# Page_1.net
KiCad netlist of a schematic drawn in Altium Designer
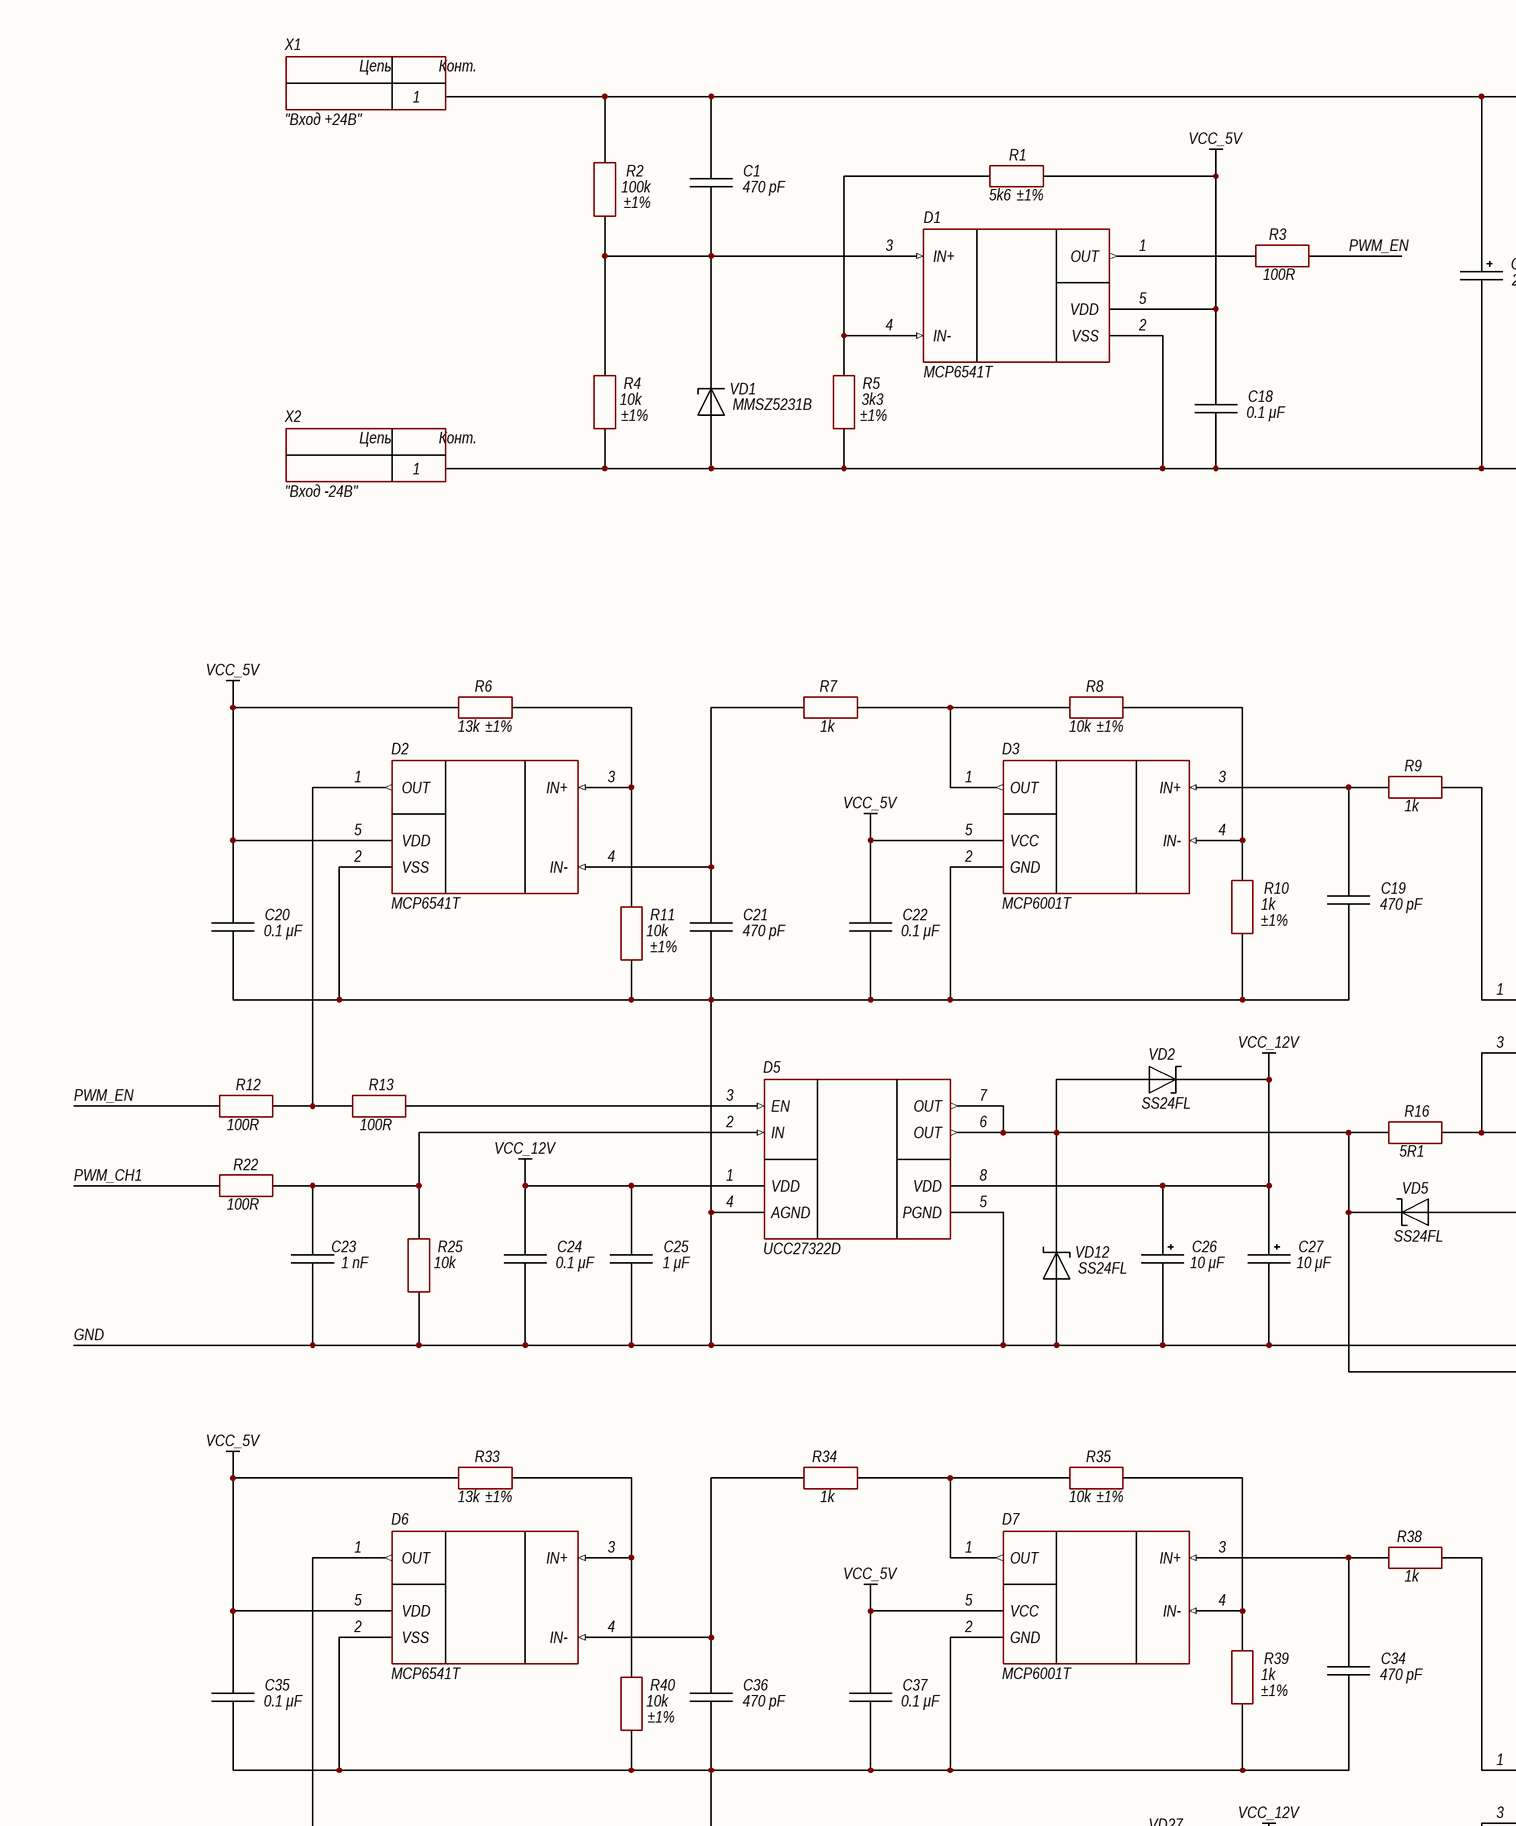
[diagram p0: Page 1.SchDoc, top left]
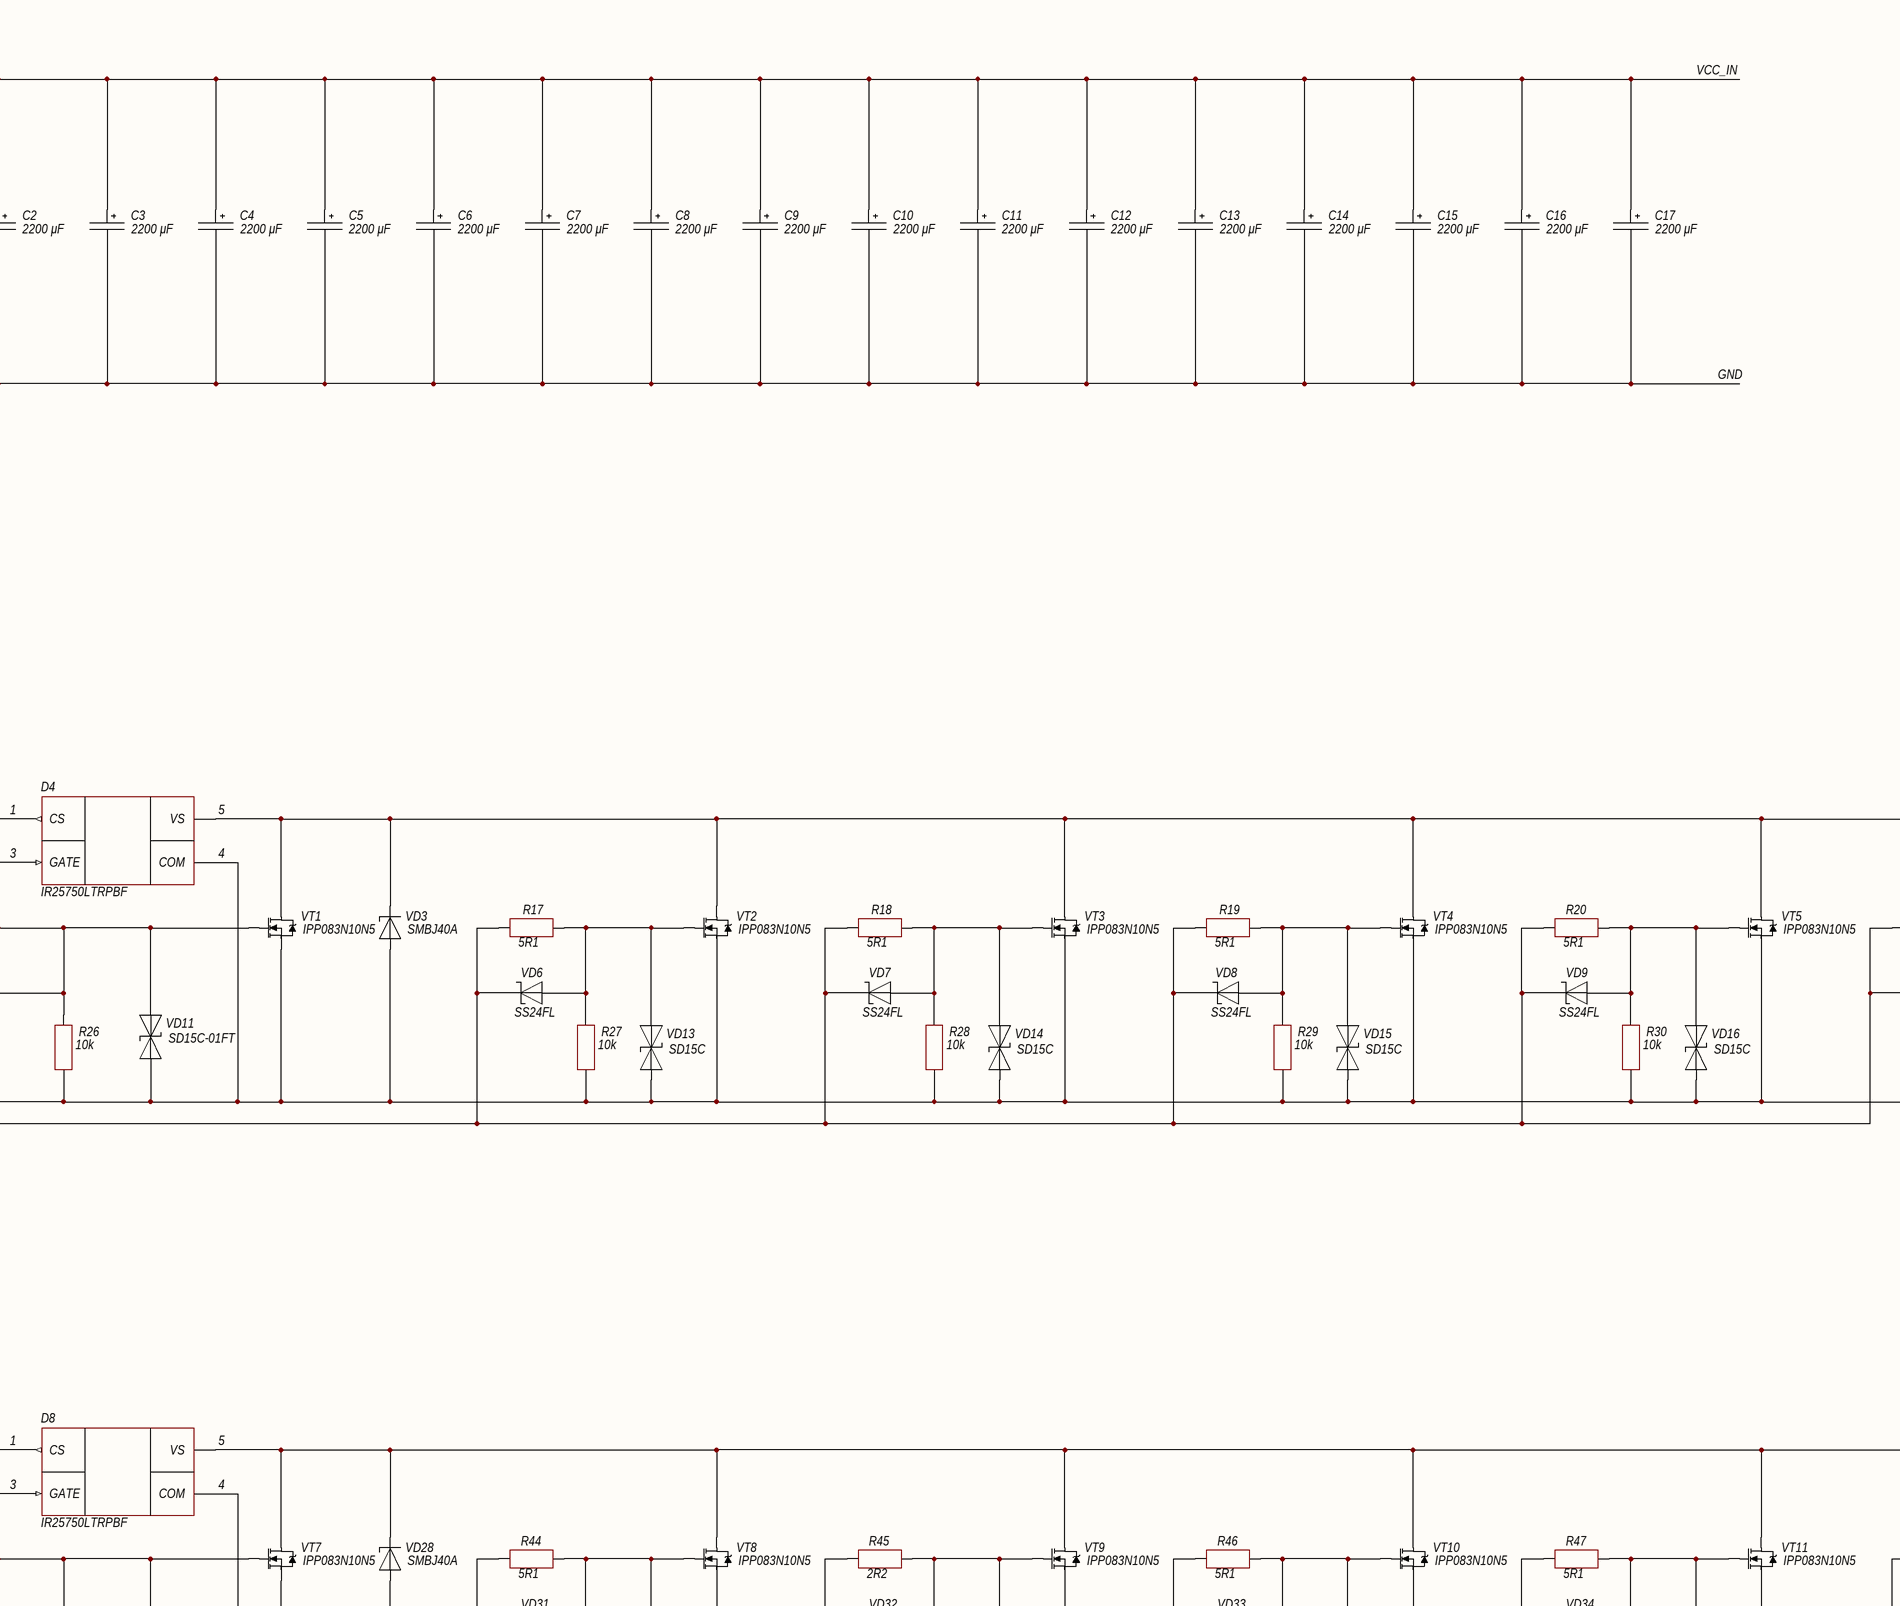
[diagram p1: Page 1.SchDoc, top middle]
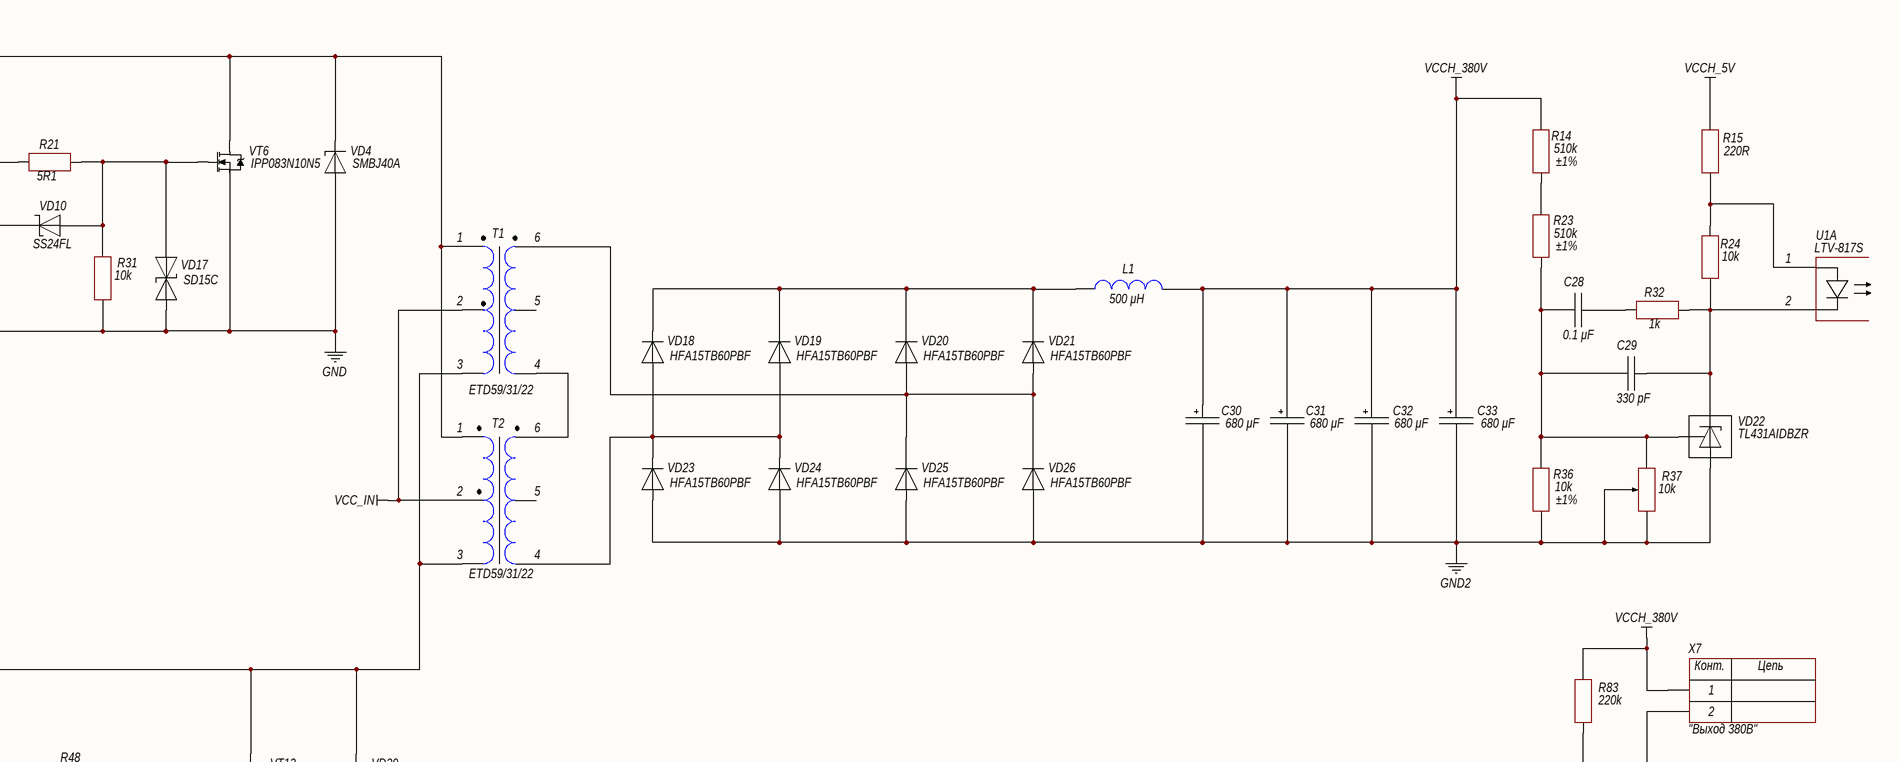
[diagram p2: Page 1.SchDoc, top right]
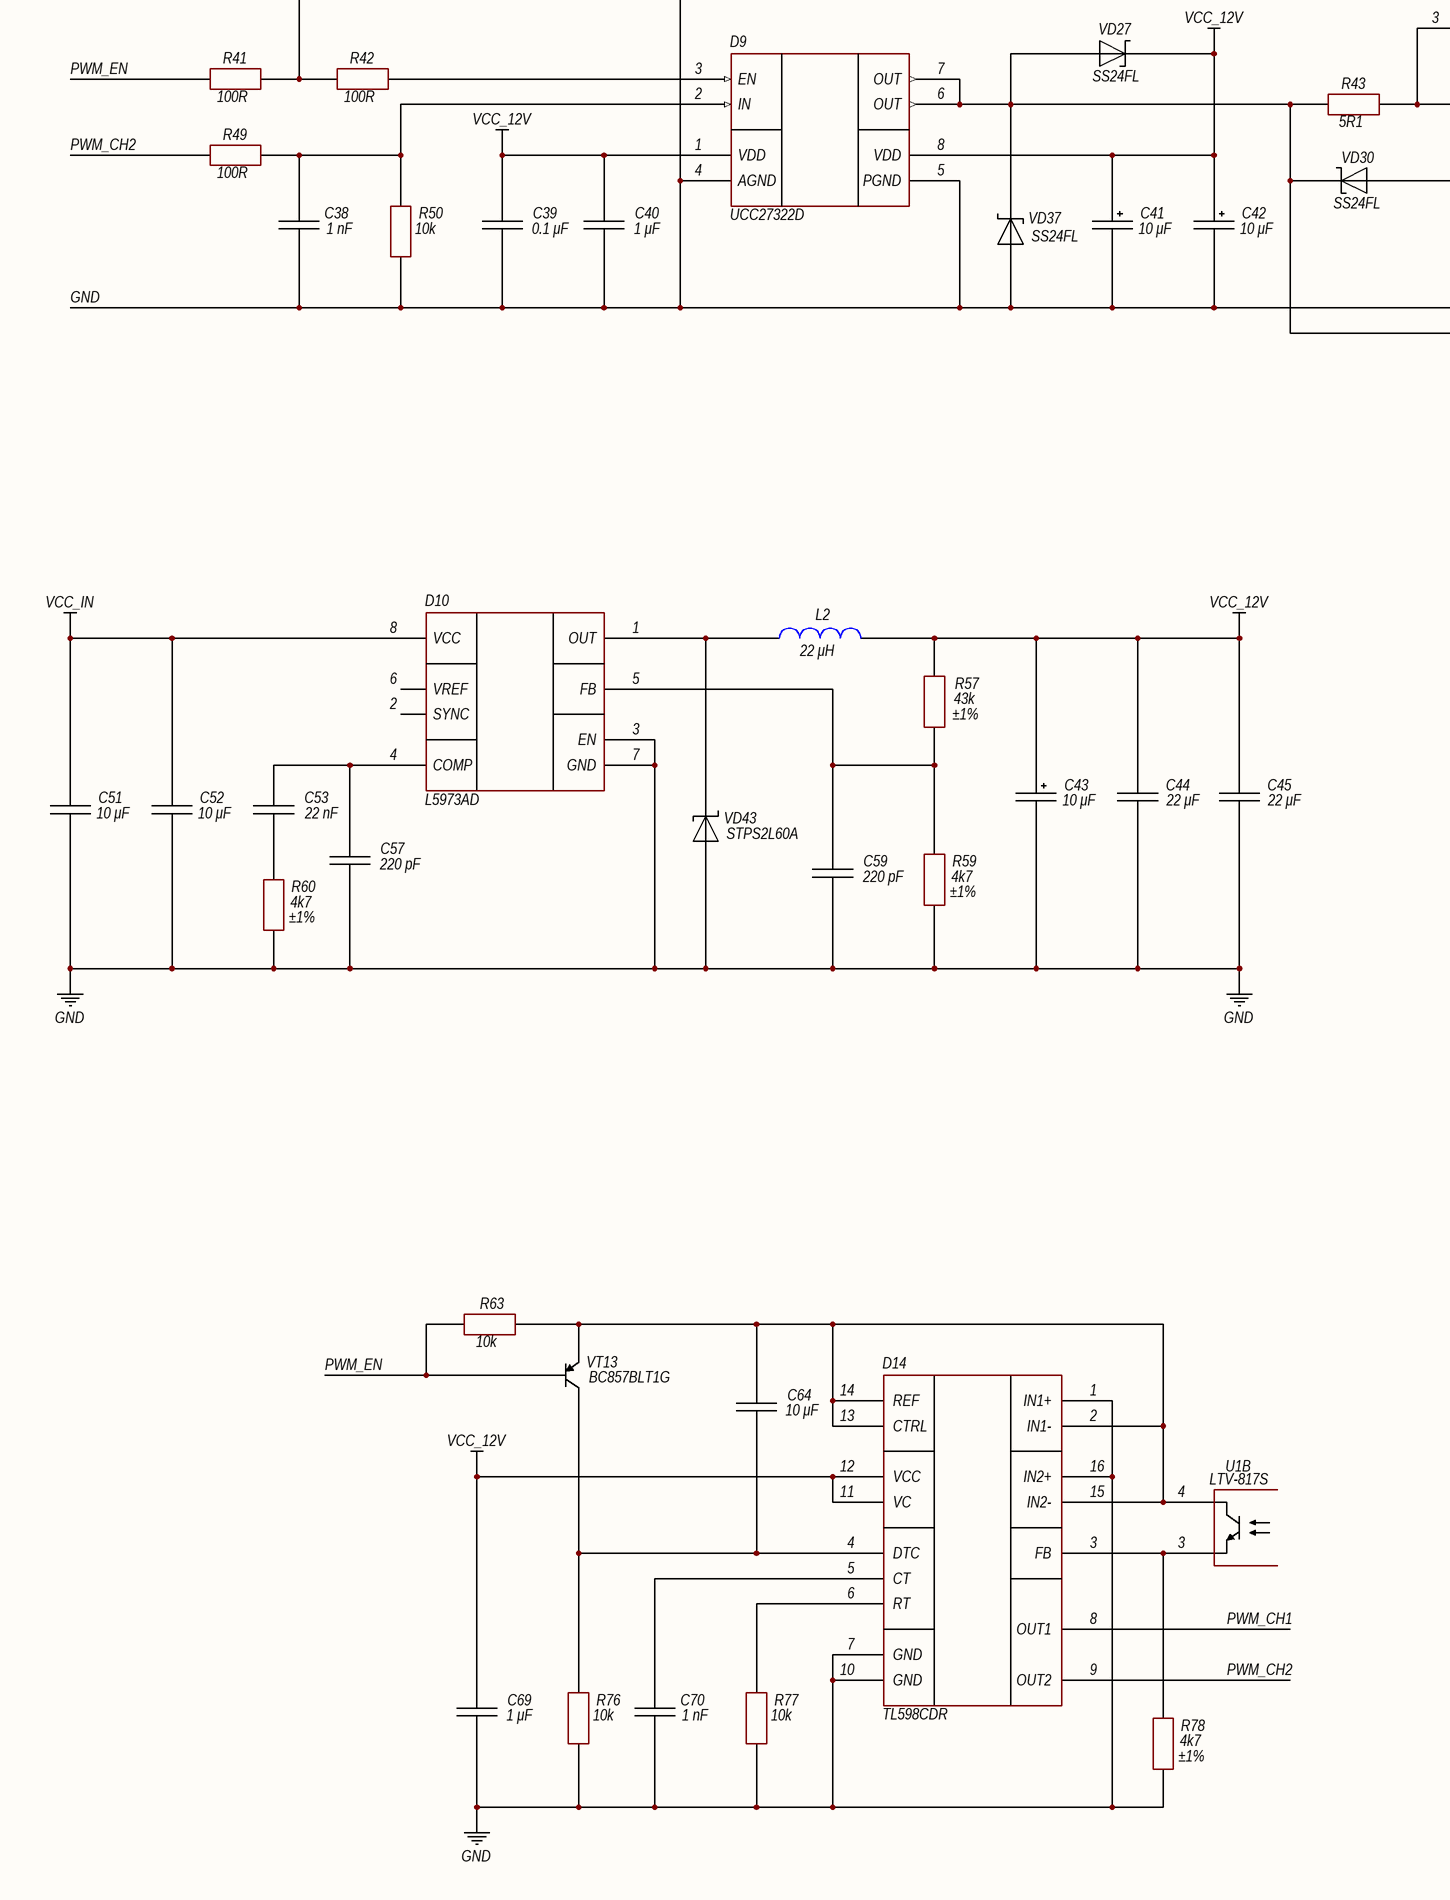
[diagram p3: Page 1.SchDoc, bottom left]
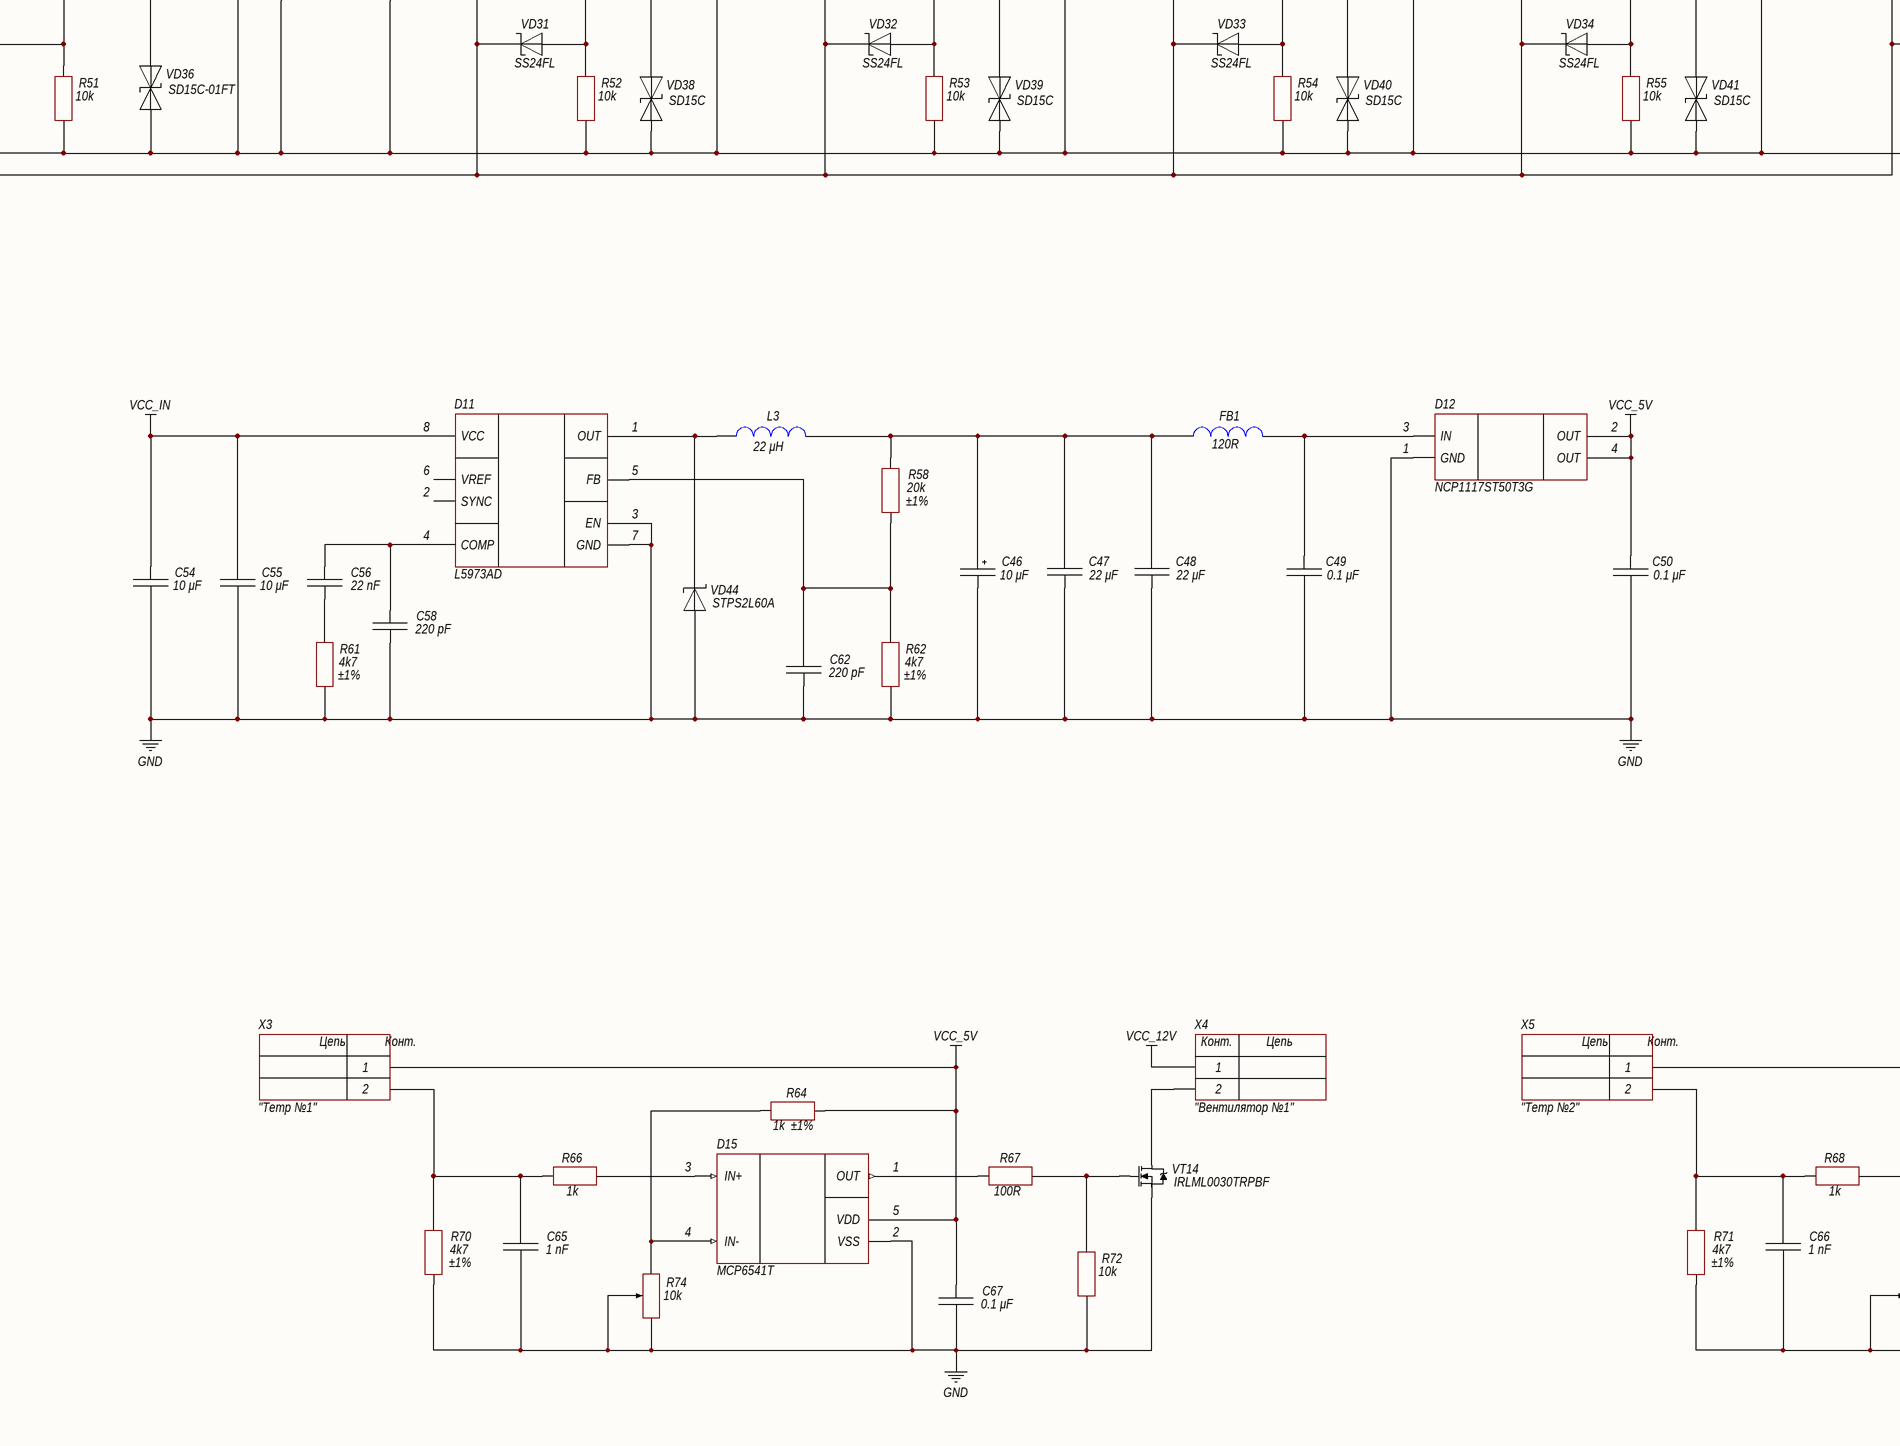
[diagram p4: Page 1.SchDoc, bottom middle]
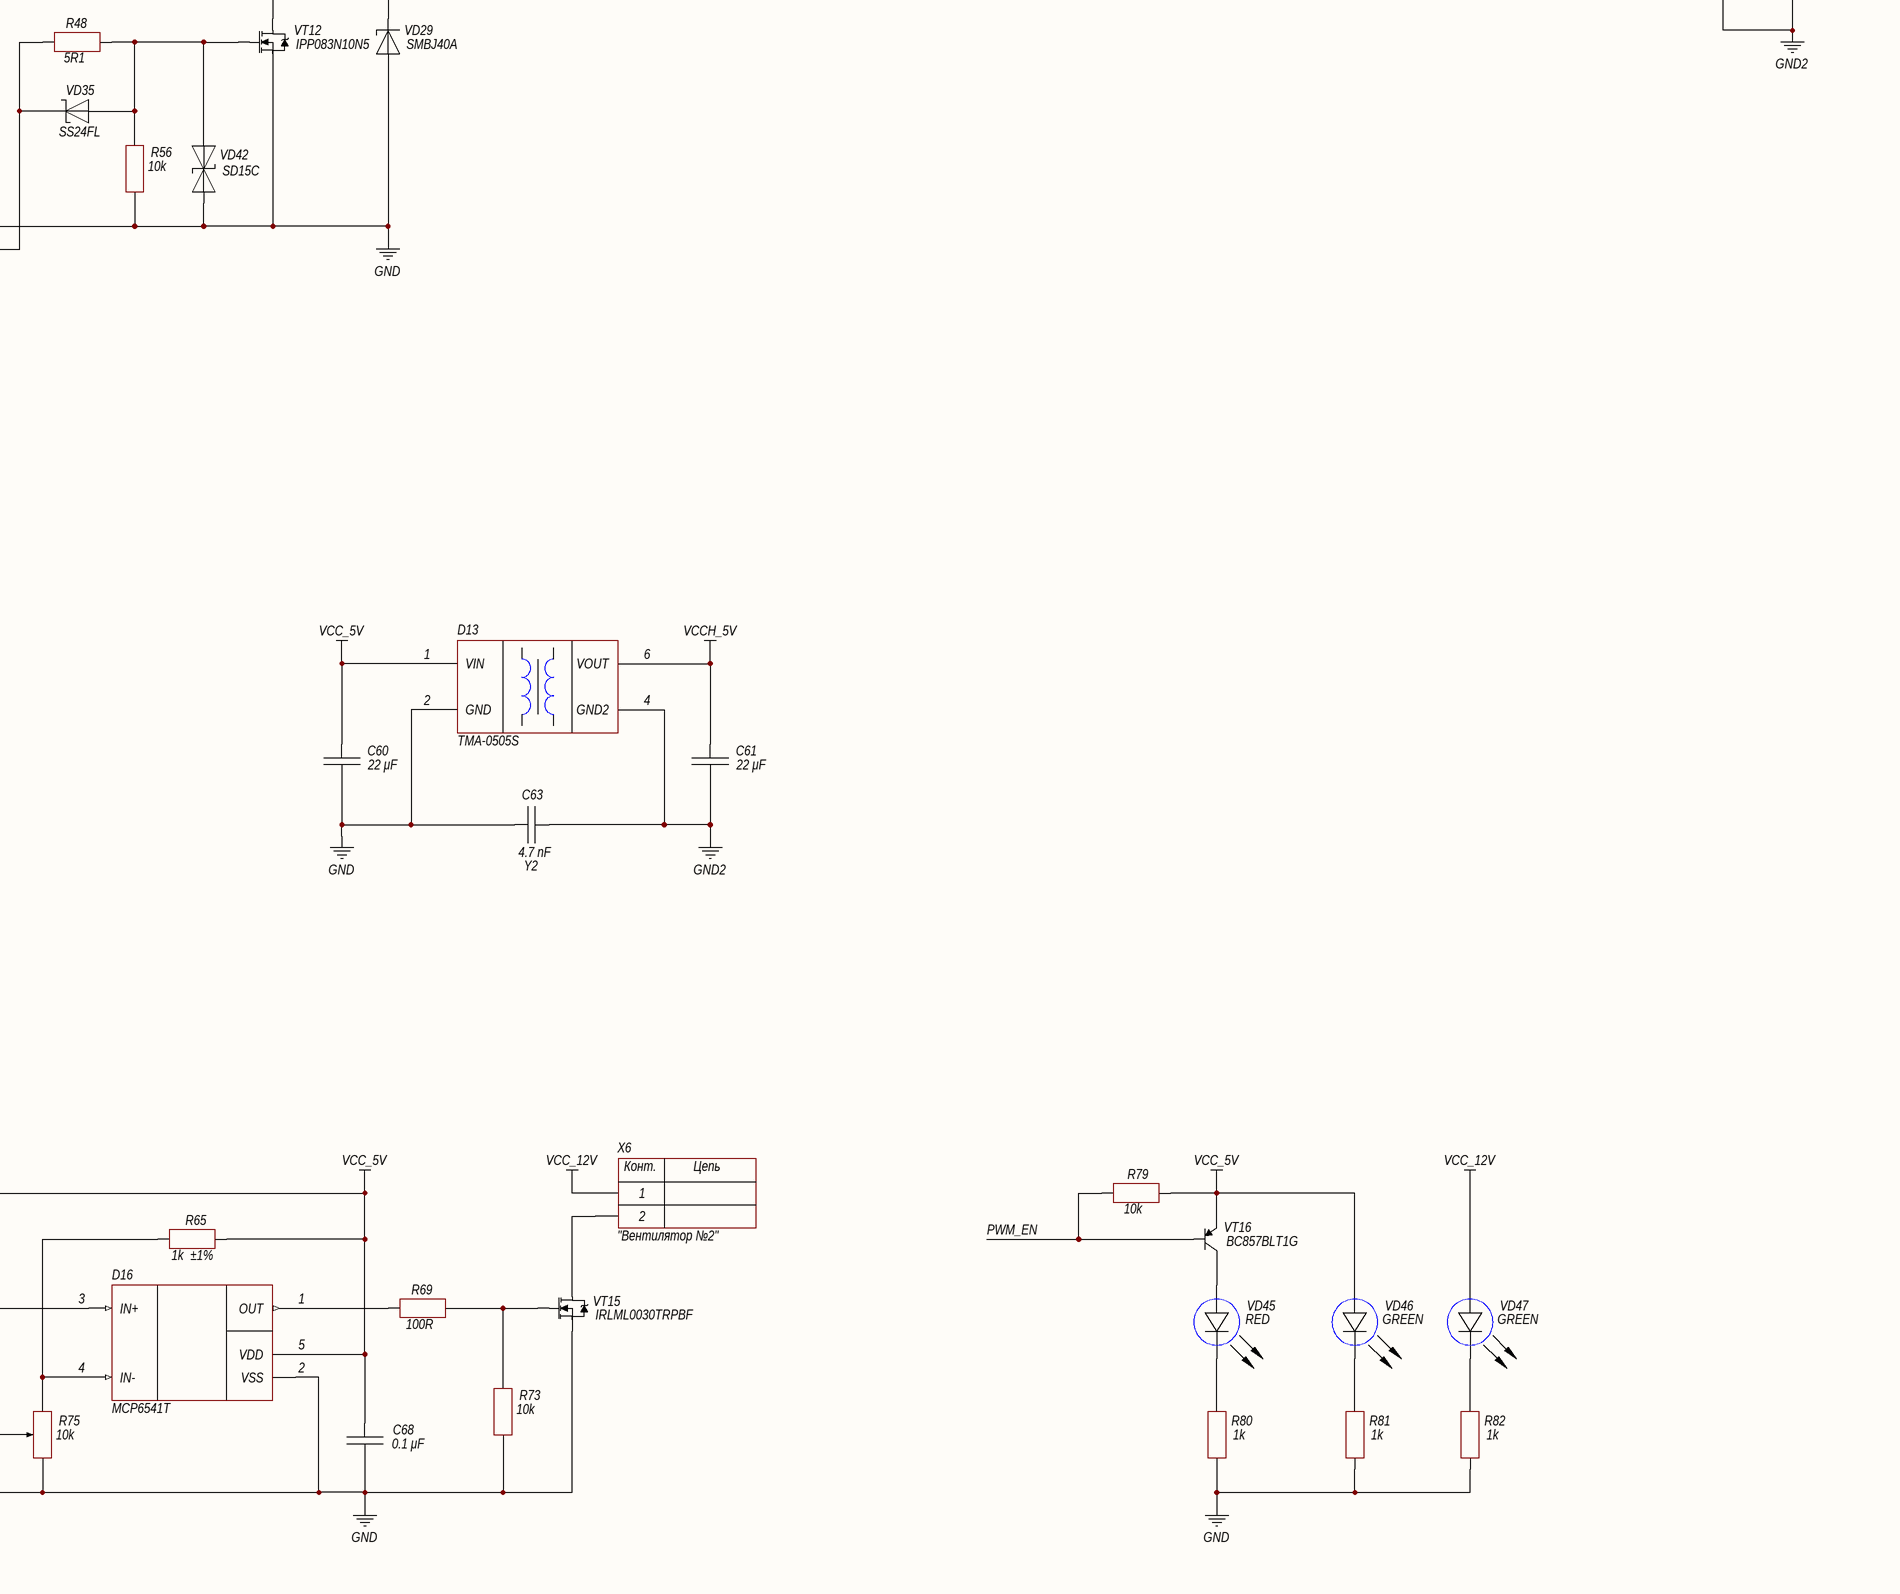
[diagram p5: Page 1.SchDoc, bottom right]

(export (version "E")
  (design (tool "Eeschema 10.0.6"))
  (components
    (comp (ref "C1")
      (value "470 pF")
      (footprint "CH0805C")
      (fields (field (name "MANUFACTURER") "Yageo"))
      (libsource (lib "Discrete") (part "Capacitor"))
    )
    (comp (ref "C2")
      (value "2200 μF")
      (footprint "D16C7.5H25")
      (fields (field (name "MANUFACTURER") "Epcos"))
      (libsource (lib "Discrete") (part "AlumCap"))
    )
    (comp (ref "C3")
      (value "2200 μF")
      (footprint "D16C7.5H25")
      (fields (field (name "MANUFACTURER") "Epcos"))
      (libsource (lib "Discrete") (part "AlumCap"))
    )
    (comp (ref "C4")
      (value "2200 μF")
      (footprint "D16C7.5H25")
      (fields (field (name "MANUFACTURER") "Epcos"))
      (libsource (lib "Discrete") (part "AlumCap"))
    )
    (comp (ref "C5")
      (value "2200 μF")
      (footprint "D16C7.5H25")
      (fields (field (name "MANUFACTURER") "Epcos"))
      (libsource (lib "Discrete") (part "AlumCap"))
    )
    (comp (ref "C6")
      (value "2200 μF")
      (footprint "D16C7.5H25")
      (fields (field (name "MANUFACTURER") "Epcos"))
      (libsource (lib "Discrete") (part "AlumCap"))
    )
    (comp (ref "C7")
      (value "2200 μF")
      (footprint "D16C7.5H25")
      (fields (field (name "MANUFACTURER") "Epcos"))
      (libsource (lib "Discrete") (part "AlumCap"))
    )
    (comp (ref "C8")
      (value "2200 μF")
      (footprint "D16C7.5H25")
      (fields (field (name "MANUFACTURER") "Epcos"))
      (libsource (lib "Discrete") (part "AlumCap"))
    )
    (comp (ref "C9")
      (value "2200 μF")
      (footprint "D16C7.5H25")
      (fields (field (name "MANUFACTURER") "Epcos"))
      (libsource (lib "Discrete") (part "AlumCap"))
    )
    (comp (ref "C10")
      (value "2200 μF")
      (footprint "D16C7.5H25")
      (fields (field (name "MANUFACTURER") "Epcos"))
      (libsource (lib "Discrete") (part "AlumCap"))
    )
    (comp (ref "C11")
      (value "2200 μF")
      (footprint "D16C7.5H25")
      (fields (field (name "MANUFACTURER") "Epcos"))
      (libsource (lib "Discrete") (part "AlumCap"))
    )
    (comp (ref "C12")
      (value "2200 μF")
      (footprint "D16C7.5H25")
      (fields (field (name "MANUFACTURER") "Epcos"))
      (libsource (lib "Discrete") (part "AlumCap"))
    )
    (comp (ref "C13")
      (value "2200 μF")
      (footprint "D16C7.5H25")
      (fields (field (name "MANUFACTURER") "Epcos"))
      (libsource (lib "Discrete") (part "AlumCap"))
    )
    (comp (ref "C14")
      (value "2200 μF")
      (footprint "D16C7.5H25")
      (fields (field (name "MANUFACTURER") "Epcos"))
      (libsource (lib "Discrete") (part "AlumCap"))
    )
    (comp (ref "C15")
      (value "2200 μF")
      (footprint "D16C7.5H25")
      (fields (field (name "MANUFACTURER") "Epcos"))
      (libsource (lib "Discrete") (part "AlumCap"))
    )
    (comp (ref "C16")
      (value "2200 μF")
      (footprint "D16C7.5H25")
      (fields (field (name "MANUFACTURER") "Epcos"))
      (libsource (lib "Discrete") (part "AlumCap"))
    )
    (comp (ref "C17")
      (value "2200 μF")
      (footprint "D16C7.5H25")
      (fields (field (name "MANUFACTURER") "Epcos"))
      (libsource (lib "Discrete") (part "AlumCap"))
    )
    (comp (ref "C18")
      (value "0.1 μF")
      (footprint "CH0805C")
      (fields (field (name "MANUFACTURER") "Yageo"))
      (libsource (lib "Discrete") (part "Capacitor"))
    )
    (comp (ref "C19")
      (value "470 pF")
      (footprint "CH0805C")
      (fields (field (name "MANUFACTURER") "Yageo"))
      (libsource (lib "Discrete") (part "Capacitor"))
    )
    (comp (ref "C20")
      (value "0.1 μF")
      (footprint "CH0805C")
      (fields (field (name "MANUFACTURER") "Yageo"))
      (libsource (lib "Discrete") (part "Capacitor"))
    )
    (comp (ref "C21")
      (value "470 pF")
      (footprint "CH0805C")
      (fields (field (name "MANUFACTURER") "Yageo"))
      (libsource (lib "Discrete") (part "Capacitor"))
    )
    (comp (ref "C22")
      (value "0.1 μF")
      (footprint "CH0805C")
      (fields (field (name "MANUFACTURER") "Yageo"))
      (libsource (lib "Discrete") (part "Capacitor"))
    )
    (comp (ref "C23")
      (value "1 nF")
      (footprint "CH0805C")
      (fields (field (name "MANUFACTURER") "Yageo"))
      (libsource (lib "Discrete") (part "Capacitor"))
    )
    (comp (ref "C24")
      (value "0.1 μF")
      (footprint "CH0805C")
      (fields (field (name "MANUFACTURER") "Yageo"))
      (libsource (lib "Discrete") (part "Capacitor"))
    )
    (comp (ref "C25")
      (value "1 μF")
      (footprint "CH0805C")
      (fields (field (name "MANUFACTURER") "Yageo"))
      (libsource (lib "Discrete") (part "Capacitor"))
    )
    (comp (ref "C26")
      (value "10 μF")
      (footprint "TANTAL_C")
      (fields (field (name "MANUFACTURER") "Vishay Sprague"))
      (libsource (lib "Discrete") (part "TantalCap"))
    )
    (comp (ref "C27")
      (value "10 μF")
      (footprint "TANTAL_C")
      (fields (field (name "MANUFACTURER") "Vishay Sprague"))
      (libsource (lib "Discrete") (part "TantalCap"))
    )
    (comp (ref "C28")
      (value "0.1 μF")
      (footprint "CH0805C")
      (fields (field (name "MANUFACTURER") "Yageo"))
      (libsource (lib "Discrete") (part "Capacitor"))
    )
    (comp (ref "C29")
      (value "330 pF")
      (footprint "CH0805C")
      (fields (field (name "MANUFACTURER") "Yageo"))
      (libsource (lib "Discrete") (part "Capacitor"))
    )
    (comp (ref "C30")
      (value "680 μF")
      (footprint "D35C10.5H50")
      (fields (field (name "MANUFACTURER") "EPCOS"))
      (libsource (lib "Discrete") (part "AlumCap"))
    )
    (comp (ref "C31")
      (value "680 μF")
      (footprint "D35C10.5H50")
      (fields (field (name "MANUFACTURER") "EPCOS"))
      (libsource (lib "Discrete") (part "AlumCap"))
    )
    (comp (ref "C32")
      (value "680 μF")
      (footprint "D35C10.5H50")
      (fields (field (name "MANUFACTURER") "EPCOS"))
      (libsource (lib "Discrete") (part "AlumCap"))
    )
    (comp (ref "C33")
      (value "680 μF")
      (footprint "D35C10.5H50")
      (fields (field (name "MANUFACTURER") "EPCOS"))
      (libsource (lib "Discrete") (part "AlumCap"))
    )
    (comp (ref "C34")
      (value "470 pF")
      (footprint "CH0805C")
      (fields (field (name "MANUFACTURER") "Yageo"))
      (libsource (lib "Discrete") (part "Capacitor"))
    )
    (comp (ref "C35")
      (value "0.1 μF")
      (footprint "CH0805C")
      (fields (field (name "MANUFACTURER") "Yageo"))
      (libsource (lib "Discrete") (part "Capacitor"))
    )
    (comp (ref "C36")
      (value "470 pF")
      (footprint "CH0805C")
      (fields (field (name "MANUFACTURER") "Yageo"))
      (libsource (lib "Discrete") (part "Capacitor"))
    )
    (comp (ref "C37")
      (value "0.1 μF")
      (footprint "CH0805C")
      (fields (field (name "MANUFACTURER") "Yageo"))
      (libsource (lib "Discrete") (part "Capacitor"))
    )
    (comp (ref "C38")
      (value "1 nF")
      (footprint "CH0805C")
      (fields (field (name "MANUFACTURER") "Yageo"))
      (libsource (lib "Discrete") (part "Capacitor"))
    )
    (comp (ref "C39")
      (value "0.1 μF")
      (footprint "CH0805C")
      (fields (field (name "MANUFACTURER") "Yageo"))
      (libsource (lib "Discrete") (part "Capacitor"))
    )
    (comp (ref "C40")
      (value "1 μF")
      (footprint "CH0805C")
      (fields (field (name "MANUFACTURER") "Yageo"))
      (libsource (lib "Discrete") (part "Capacitor"))
    )
    (comp (ref "C41")
      (value "10 μF")
      (footprint "TANTAL_C")
      (fields (field (name "MANUFACTURER") "Vishay Sprague"))
      (libsource (lib "Discrete") (part "TantalCap"))
    )
    (comp (ref "C42")
      (value "10 μF")
      (footprint "TANTAL_C")
      (fields (field (name "MANUFACTURER") "Vishay Sprague"))
      (libsource (lib "Discrete") (part "TantalCap"))
    )
    (comp (ref "C43")
      (value "10 μF")
      (footprint "TANTAL_C")
      (fields (field (name "MANUFACTURER") "Vishay Sprague"))
      (libsource (lib "Discrete") (part "TantalCap"))
    )
    (comp (ref "C44")
      (value "22 μF")
      (footprint "CH1206C")
      (fields (field (name "MANUFACTURER") "Yageo"))
      (libsource (lib "Discrete") (part "Capacitor"))
    )
    (comp (ref "C45")
      (value "22 μF")
      (footprint "CH1206C")
      (fields (field (name "MANUFACTURER") "Yageo"))
      (libsource (lib "Discrete") (part "Capacitor"))
    )
    (comp (ref "C46")
      (value "10 μF")
      (footprint "TANTAL_C")
      (fields (field (name "MANUFACTURER") "Vishay Sprague"))
      (libsource (lib "Discrete") (part "TantalCap"))
    )
    (comp (ref "C47")
      (value "22 μF")
      (footprint "CH1206C")
      (fields (field (name "MANUFACTURER") "Yageo"))
      (libsource (lib "Discrete") (part "Capacitor"))
    )
    (comp (ref "C48")
      (value "22 μF")
      (footprint "CH1206C")
      (fields (field (name "MANUFACTURER") "Yageo"))
      (libsource (lib "Discrete") (part "Capacitor"))
    )
    (comp (ref "C49")
      (value "0.1 μF")
      (footprint "CH0805C")
      (fields (field (name "MANUFACTURER") "Yageo"))
      (libsource (lib "Discrete") (part "Capacitor"))
    )
    (comp (ref "C50")
      (value "0.1 μF")
      (footprint "CH0805C")
      (fields (field (name "MANUFACTURER") "Yageo"))
      (libsource (lib "Discrete") (part "Capacitor"))
    )
    (comp (ref "C51")
      (value "10 μF")
      (footprint "CH1206C")
      (fields (field (name "MANUFACTURER") "Yageo"))
      (libsource (lib "Discrete") (part "Capacitor"))
    )
    (comp (ref "C52")
      (value "10 μF")
      (footprint "CH1206C")
      (fields (field (name "MANUFACTURER") "Yageo"))
      (libsource (lib "Discrete") (part "Capacitor"))
    )
    (comp (ref "C53")
      (value "22 nF")
      (footprint "CH0805C")
      (fields (field (name "MANUFACTURER") "Yageo"))
      (libsource (lib "Discrete") (part "Capacitor"))
    )
    (comp (ref "C54")
      (value "10 μF")
      (footprint "CH1206C")
      (fields (field (name "MANUFACTURER") "Yageo"))
      (libsource (lib "Discrete") (part "Capacitor"))
    )
    (comp (ref "C55")
      (value "10 μF")
      (footprint "CH1206C")
      (fields (field (name "MANUFACTURER") "Yageo"))
      (libsource (lib "Discrete") (part "Capacitor"))
    )
    (comp (ref "C56")
      (value "22 nF")
      (footprint "CH0805C")
      (fields (field (name "MANUFACTURER") "Yageo"))
      (libsource (lib "Discrete") (part "Capacitor"))
    )
    (comp (ref "C57")
      (value "220 pF")
      (footprint "CH0805C")
      (fields (field (name "MANUFACTURER") "Yageo"))
      (libsource (lib "Discrete") (part "Capacitor"))
    )
    (comp (ref "C58")
      (value "220 pF")
      (footprint "CH0805C")
      (fields (field (name "MANUFACTURER") "Yageo"))
      (libsource (lib "Discrete") (part "Capacitor"))
    )
    (comp (ref "C59")
      (value "220 pF")
      (footprint "CH0805C")
      (fields (field (name "MANUFACTURER") "Yageo"))
      (libsource (lib "Discrete") (part "Capacitor"))
    )
    (comp (ref "C60")
      (value "22 μF")
      (footprint "CH1206C")
      (fields (field (name "MANUFACTURER") "Yageo"))
      (libsource (lib "Discrete") (part "Capacitor"))
    )
    (comp (ref "C61")
      (value "22 μF")
      (footprint "CH1206C")
      (fields (field (name "MANUFACTURER") "Yageo"))
      (libsource (lib "Discrete") (part "Capacitor"))
    )
    (comp (ref "C62")
      (value "220 pF")
      (footprint "CH0805C")
      (fields (field (name "MANUFACTURER") "Yageo"))
      (libsource (lib "Discrete") (part "Capacitor"))
    )
    (comp (ref "C63")
      (value "4.7 nF")
      (footprint "CAP: B32021")
      (fields (field (name "MANUFACTURER") "EPCOS (TDK)") (field (name "COMPONENTKIND") "Y2"))
      (libsource (lib "Discrete") (part "Capacitor"))
    )
    (comp (ref "C64")
      (value "10 μF")
      (footprint "CH0805C")
      (fields (field (name "MANUFACTURER") "Yageo"))
      (libsource (lib "Discrete") (part "Capacitor"))
    )
    (comp (ref "C65")
      (value "1 nF")
      (footprint "CH0805C")
      (fields (field (name "MANUFACTURER") "Yageo"))
      (libsource (lib "Discrete") (part "Capacitor"))
    )
    (comp (ref "C66")
      (value "1 nF")
      (footprint "CH0805C")
      (fields (field (name "MANUFACTURER") "Yageo"))
      (libsource (lib "Discrete") (part "Capacitor"))
    )
    (comp (ref "C67")
      (value "0.1 μF")
      (footprint "CH0805C")
      (fields (field (name "MANUFACTURER") "Yageo"))
      (libsource (lib "Discrete") (part "Capacitor"))
    )
    (comp (ref "C68")
      (value "0.1 μF")
      (footprint "CH0805C")
      (fields (field (name "MANUFACTURER") "Yageo"))
      (libsource (lib "Discrete") (part "Capacitor"))
    )
    (comp (ref "C69")
      (value "1 μF")
      (footprint "CH0805C")
      (fields (field (name "MANUFACTURER") "Yageo"))
      (libsource (lib "Discrete") (part "Capacitor"))
    )
    (comp (ref "C70")
      (value "1 nF")
      (footprint "CH0805C")
      (fields (field (name "MANUFACTURER") "Yageo"))
      (libsource (lib "Discrete") (part "Capacitor"))
    )
    (comp (ref "D1")
      (value "MCP6541T")
      (footprint "SOT23-5")
      (description "Comparator")
      (fields (field (name "MANUFACTURER") "Microchip Technology"))
      (libsource (lib "Analog") (part "MCP6541T"))
    )
    (comp (ref "D2")
      (value "MCP6541T")
      (footprint "SOT23-5")
      (description "Comparator")
      (fields (field (name "MANUFACTURER") "Microchip Technology"))
      (libsource (lib "") (part "MCP6541T_1"))
    )
    (comp (ref "D3")
      (value "MCP6001T")
      (footprint "SOT23-5")
      (description "OP amplifier")
      (fields (field (name "MANUFACTURER") "Microchip Technology"))
      (libsource (lib "Analog") (part "MCP6001T"))
    )
    (comp (ref "D4")
      (value "IR25750LTRPBF")
      (footprint "SOT23-5")
      (description "Sensor")
      (fields (field (name "MANUFACTURER") "Infineon Technologies"))
      (libsource (lib "Power Supplies") (part "IR25750LTRPBF"))
    )
    (comp (ref "D5")
      (value "UCC27322D")
      (footprint "8-SOIC")
      (description "Low driver")
      (fields (field (name "MANUFACTURER") "Texas Instruments"))
      (libsource (lib "Power Supplies") (part "UCC27322D"))
    )
    (comp (ref "D6")
      (value "MCP6541T")
      (footprint "SOT23-5")
      (description "Comparator")
      (fields (field (name "MANUFACTURER") "Microchip Technology"))
      (libsource (lib "") (part "MCP6541T_1"))
    )
    (comp (ref "D7")
      (value "MCP6001T")
      (footprint "SOT23-5")
      (description "OP amplifier")
      (fields (field (name "MANUFACTURER") "Microchip Technology"))
      (libsource (lib "Analog") (part "MCP6001T"))
    )
    (comp (ref "D8")
      (value "IR25750LTRPBF")
      (footprint "SOT23-5")
      (description "Sensor")
      (fields (field (name "MANUFACTURER") "Infineon Technologies"))
      (libsource (lib "Power Supplies") (part "IR25750LTRPBF"))
    )
    (comp (ref "D9")
      (value "UCC27322D")
      (footprint "8-SOIC")
      (description "Low driver")
      (fields (field (name "MANUFACTURER") "Texas Instruments"))
      (libsource (lib "Power Supplies") (part "UCC27322D"))
    )
    (comp (ref "D10")
      (value "L5973AD")
      (footprint "8-SOIC (PAD)")
      (description "Step-down")
      (fields (field (name "MANUFACTURER") "STMicroelectronics"))
      (libsource (lib "Power Supplies") (part "L5973AD"))
    )
    (comp (ref "D11")
      (value "L5973AD")
      (footprint "8-SOIC (PAD)")
      (description "Step-down")
      (fields (field (name "MANUFACTURER") "STMicroelectronics"))
      (libsource (lib "Power Supplies") (part "L5973AD"))
    )
    (comp (ref "D12")
      (value "NCP1117ST50T3G")
      (footprint "SOT223")
      (description "LDO")
      (fields (field (name "MANUFACTURER") "ON Semiconductor"))
      (libsource (lib "Power Supplies") (part "NCP1117LPST50T3G"))
    )
    (comp (ref "D13")
      (value "TMA-0505S")
      (footprint "MOD: TMA-0505S")
      (description "Isolator DC")
      (fields (field (name "MANUFACTURER") "Traco Power"))
      (libsource (lib "Module") (part "TMA-0505S"))
    )
    (comp (ref "D14")
      (value "TL598CDR")
      (footprint "16-SOIC")
      (description "PWM")
      (fields (field (name "MANUFACTURER") "Texas Instruments"))
      (libsource (lib "Power Supplies") (part "TL598CDR"))
    )
    (comp (ref "D15")
      (value "MCP6541T")
      (footprint "SOT23-5")
      (description "Comparator")
      (fields (field (name "MANUFACTURER") "Microchip Technology"))
      (libsource (lib "Analog") (part "MCP6541T"))
    )
    (comp (ref "D16")
      (value "MCP6541T")
      (footprint "SOT23-5")
      (description "Comparator")
      (fields (field (name "MANUFACTURER") "Microchip Technology"))
      (libsource (lib "Analog") (part "MCP6541T"))
    )
    (comp (ref "FB1")
      (value "120R")
      (footprint "CH0805L")
      (fields (field (name "MANUFACTURER") "Murata Electronics North America"))
      (libsource (lib "Discrete") (part "Inductor"))
    )
    (comp (ref "L1")
      (value "500 μH")
      (footprint "IND: R46")
      (fields (field (name "MANUFACTURER") "Magnetics"))
      (libsource (lib "Transformers") (part "Inductor ring"))
    )
    (comp (ref "L2")
      (value "22 μH")
      (footprint "IND: SDR0604")
      (fields (field (name "MANUFACTURER") "Bourns Inc."))
      (libsource (lib "Discrete") (part "Inductor"))
    )
    (comp (ref "L3")
      (value "22 μH")
      (footprint "IND: SDR0604")
      (fields (field (name "MANUFACTURER") "Bourns Inc."))
      (libsource (lib "Discrete") (part "Inductor"))
    )
    (comp (ref "R1")
      (value "5k6")
      (footprint "CH0805R")
      (fields (field (name "MANUFACTURER") "Yageo") (field (name "COMPONENTKIND") "±1%"))
      (libsource (lib "") (part "Resistor_3"))
    )
    (comp (ref "R2")
      (value "100k")
      (footprint "CH0805R")
      (fields (field (name "MANUFACTURER") "Yageo") (field (name "COMPONENTKIND") "±1%"))
      (libsource (lib "") (part "Resistor_2"))
    )
    (comp (ref "R3")
      (value "100R")
      (footprint "CH0805R")
      (fields (field (name "MANUFACTURER") "Yageo"))
      (libsource (lib "Discrete") (part "Resistor"))
    )
    (comp (ref "R4")
      (value "10k")
      (footprint "CH0805R")
      (fields (field (name "MANUFACTURER") "Yageo") (field (name "COMPONENTKIND") "±1%"))
      (libsource (lib "") (part "Resistor_2"))
    )
    (comp (ref "R5")
      (value "3k3")
      (footprint "CH0805R")
      (fields (field (name "MANUFACTURER") "Yageo") (field (name "COMPONENTKIND") "±1%"))
      (libsource (lib "") (part "Resistor_2"))
    )
    (comp (ref "R6")
      (value "13k")
      (footprint "CH0805R")
      (fields (field (name "MANUFACTURER") "Yageo") (field (name "COMPONENTKIND") "±1%"))
      (libsource (lib "Discrete") (part "Resistor"))
    )
    (comp (ref "R7")
      (value "1k")
      (footprint "CH0805R")
      (fields (field (name "MANUFACTURER") "Yageo"))
      (libsource (lib "") (part "Resistor_2"))
    )
    (comp (ref "R8")
      (value "10k")
      (footprint "CH0805R")
      (fields (field (name "MANUFACTURER") "Yageo") (field (name "COMPONENTKIND") "±1%"))
      (libsource (lib "Discrete") (part "Resistor"))
    )
    (comp (ref "R9")
      (value "1k")
      (footprint "CH0805R")
      (fields (field (name "MANUFACTURER") "Yageo"))
      (libsource (lib "") (part "Resistor_2"))
    )
    (comp (ref "R10")
      (value "1k")
      (footprint "CH0805R")
      (fields (field (name "MANUFACTURER") "Yageo") (field (name "COMPONENTKIND") "±1%"))
      (libsource (lib "") (part "Resistor_2"))
    )
    (comp (ref "R11")
      (value "10k")
      (footprint "CH0805R")
      (fields (field (name "MANUFACTURER") "Yageo") (field (name "COMPONENTKIND") "±1%"))
      (libsource (lib "") (part "Resistor_2"))
    )
    (comp (ref "R12")
      (value "100R")
      (footprint "CH0805R")
      (fields (field (name "MANUFACTURER") "Yageo"))
      (libsource (lib "Discrete") (part "Resistor"))
    )
    (comp (ref "R13")
      (value "100R")
      (footprint "CH0805R")
      (fields (field (name "MANUFACTURER") "Yageo"))
      (libsource (lib "Discrete") (part "Resistor"))
    )
    (comp (ref "R14")
      (value "510k")
      (footprint "CH0805R")
      (fields (field (name "MANUFACTURER") "Yageo") (field (name "COMPONENTKIND") "±1%"))
      (libsource (lib "Discrete") (part "Resistor"))
    )
    (comp (ref "R15")
      (value "220R")
      (footprint "CH0805R")
      (fields (field (name "MANUFACTURER") "Yageo"))
      (libsource (lib "") (part "Resistor_3"))
    )
    (comp (ref "R16")
      (value "5R1")
      (footprint "CH0805R")
      (fields (field (name "MANUFACTURER") "Yageo"))
      (libsource (lib "Discrete") (part "Resistor"))
    )
    (comp (ref "R17")
      (value "5R1")
      (footprint "CH0805R")
      (fields (field (name "MANUFACTURER") "Yageo"))
      (libsource (lib "Discrete") (part "Resistor"))
    )
    (comp (ref "R18")
      (value "5R1")
      (footprint "CH0805R")
      (fields (field (name "MANUFACTURER") "Yageo"))
      (libsource (lib "Discrete") (part "Resistor"))
    )
    (comp (ref "R19")
      (value "5R1")
      (footprint "CH0805R")
      (fields (field (name "MANUFACTURER") "Yageo"))
      (libsource (lib "Discrete") (part "Resistor"))
    )
    (comp (ref "R20")
      (value "5R1")
      (footprint "CH0805R")
      (fields (field (name "MANUFACTURER") "Yageo"))
      (libsource (lib "Discrete") (part "Resistor"))
    )
    (comp (ref "R21")
      (value "5R1")
      (footprint "CH0805R")
      (fields (field (name "MANUFACTURER") "Yageo"))
      (libsource (lib "Discrete") (part "Resistor"))
    )
    (comp (ref "R22")
      (value "100R")
      (footprint "CH0805R")
      (fields (field (name "MANUFACTURER") "Yageo"))
      (libsource (lib "Discrete") (part "Resistor"))
    )
    (comp (ref "R23")
      (value "510k")
      (footprint "CH0805R")
      (fields (field (name "MANUFACTURER") "Yageo") (field (name "COMPONENTKIND") "±1%"))
      (libsource (lib "Discrete") (part "Resistor"))
    )
    (comp (ref "R24")
      (value "10k")
      (footprint "CH0805R")
      (fields (field (name "MANUFACTURER") "Yageo"))
      (libsource (lib "") (part "Resistor_3"))
    )
    (comp (ref "R25")
      (value "10k")
      (footprint "CH0805R")
      (fields (field (name "MANUFACTURER") "Yageo"))
      (libsource (lib "") (part "Resistor_1"))
    )
    (comp (ref "R26")
      (value "10k")
      (footprint "CH0805R")
      (fields (field (name "MANUFACTURER") "Yageo"))
      (libsource (lib "") (part "Resistor_1"))
    )
    (comp (ref "R27")
      (value "10k")
      (footprint "CH0805R")
      (fields (field (name "MANUFACTURER") "Yageo"))
      (libsource (lib "") (part "Resistor_1"))
    )
    (comp (ref "R28")
      (value "10k")
      (footprint "CH0805R")
      (fields (field (name "MANUFACTURER") "Yageo"))
      (libsource (lib "") (part "Resistor_1"))
    )
    (comp (ref "R29")
      (value "10k")
      (footprint "CH0805R")
      (fields (field (name "MANUFACTURER") "Yageo"))
      (libsource (lib "") (part "Resistor_1"))
    )
    (comp (ref "R30")
      (value "10k")
      (footprint "CH0805R")
      (fields (field (name "MANUFACTURER") "Yageo"))
      (libsource (lib "") (part "Resistor_1"))
    )
    (comp (ref "R31")
      (value "10k")
      (footprint "CH0805R")
      (fields (field (name "MANUFACTURER") "Yageo"))
      (libsource (lib "") (part "Resistor_1"))
    )
    (comp (ref "R32")
      (value "1k")
      (footprint "CH0805R")
      (fields (field (name "MANUFACTURER") "Yageo"))
      (libsource (lib "") (part "Resistor_2"))
    )
    (comp (ref "R33")
      (value "13k")
      (footprint "CH0805R")
      (fields (field (name "MANUFACTURER") "Yageo") (field (name "COMPONENTKIND") "±1%"))
      (libsource (lib "Discrete") (part "Resistor"))
    )
    (comp (ref "R34")
      (value "1k")
      (footprint "CH0805R")
      (fields (field (name "MANUFACTURER") "Yageo"))
      (libsource (lib "") (part "Resistor_2"))
    )
    (comp (ref "R35")
      (value "10k")
      (footprint "CH0805R")
      (fields (field (name "MANUFACTURER") "Yageo") (field (name "COMPONENTKIND") "±1%"))
      (libsource (lib "Discrete") (part "Resistor"))
    )
    (comp (ref "R36")
      (value "10k")
      (footprint "CH0805R")
      (fields (field (name "MANUFACTURER") "Yageo") (field (name "COMPONENTKIND") "±1%"))
      (libsource (lib "Discrete") (part "Resistor"))
    )
    (comp (ref "R37")
      (value "10k")
      (footprint "RES: 3296W")
      (fields (field (name "MANUFACTURER") "Bourns Inc."))
      (libsource (lib "Discrete") (part "ADJ resistor"))
    )
    (comp (ref "R38")
      (value "1k")
      (footprint "CH0805R")
      (fields (field (name "MANUFACTURER") "Yageo"))
      (libsource (lib "") (part "Resistor_2"))
    )
    (comp (ref "R39")
      (value "1k")
      (footprint "CH0805R")
      (fields (field (name "MANUFACTURER") "Yageo") (field (name "COMPONENTKIND") "±1%"))
      (libsource (lib "") (part "Resistor_2"))
    )
    (comp (ref "R40")
      (value "10k")
      (footprint "CH0805R")
      (fields (field (name "MANUFACTURER") "Yageo") (field (name "COMPONENTKIND") "±1%"))
      (libsource (lib "") (part "Resistor_2"))
    )
    (comp (ref "R41")
      (value "100R")
      (footprint "CH0805R")
      (fields (field (name "MANUFACTURER") "Yageo"))
      (libsource (lib "Discrete") (part "Resistor"))
    )
    (comp (ref "R42")
      (value "100R")
      (footprint "CH0805R")
      (fields (field (name "MANUFACTURER") "Yageo"))
      (libsource (lib "Discrete") (part "Resistor"))
    )
    (comp (ref "R43")
      (value "5R1")
      (footprint "CH0805R")
      (fields (field (name "MANUFACTURER") "Yageo"))
      (libsource (lib "Discrete") (part "Resistor"))
    )
    (comp (ref "R44")
      (value "5R1")
      (footprint "CH0805R")
      (fields (field (name "MANUFACTURER") "Yageo"))
      (libsource (lib "Discrete") (part "Resistor"))
    )
    (comp (ref "R45")
      (value "2R2")
      (footprint "CH0805R")
      (fields (field (name "MANUFACTURER") "Yageo"))
      (libsource (lib "Discrete") (part "Resistor"))
    )
    (comp (ref "R46")
      (value "5R1")
      (footprint "CH0805R")
      (fields (field (name "MANUFACTURER") "Yageo"))
      (libsource (lib "Discrete") (part "Resistor"))
    )
    (comp (ref "R47")
      (value "5R1")
      (footprint "CH0805R")
      (fields (field (name "MANUFACTURER") "Yageo"))
      (libsource (lib "Discrete") (part "Resistor"))
    )
    (comp (ref "R48")
      (value "5R1")
      (footprint "CH0805R")
      (fields (field (name "MANUFACTURER") "Yageo"))
      (libsource (lib "Discrete") (part "Resistor"))
    )
    (comp (ref "R49")
      (value "100R")
      (footprint "CH0805R")
      (fields (field (name "MANUFACTURER") "Yageo"))
      (libsource (lib "Discrete") (part "Resistor"))
    )
    (comp (ref "R50")
      (value "10k")
      (footprint "CH0805R")
      (fields (field (name "MANUFACTURER") "Yageo"))
      (libsource (lib "") (part "Resistor_1"))
    )
    (comp (ref "R51")
      (value "10k")
      (footprint "CH0805R")
      (fields (field (name "MANUFACTURER") "Yageo"))
      (libsource (lib "") (part "Resistor_1"))
    )
    (comp (ref "R52")
      (value "10k")
      (footprint "CH0805R")
      (fields (field (name "MANUFACTURER") "Yageo"))
      (libsource (lib "") (part "Resistor_1"))
    )
    (comp (ref "R53")
      (value "10k")
      (footprint "CH0805R")
      (fields (field (name "MANUFACTURER") "Yageo"))
      (libsource (lib "") (part "Resistor_1"))
    )
    (comp (ref "R54")
      (value "10k")
      (footprint "CH0805R")
      (fields (field (name "MANUFACTURER") "Yageo"))
      (libsource (lib "") (part "Resistor_1"))
    )
    (comp (ref "R55")
      (value "10k")
      (footprint "CH0805R")
      (fields (field (name "MANUFACTURER") "Yageo"))
      (libsource (lib "") (part "Resistor_1"))
    )
    (comp (ref "R56")
      (value "10k")
      (footprint "CH0805R")
      (fields (field (name "MANUFACTURER") "Yageo"))
      (libsource (lib "") (part "Resistor_1"))
    )
    (comp (ref "R57")
      (value "43k")
      (footprint "CH0805R")
      (fields (field (name "MANUFACTURER") "Yageo") (field (name "COMPONENTKIND") "±1%"))
      (libsource (lib "") (part "Resistor_2"))
    )
    (comp (ref "R58")
      (value "20k")
      (footprint "CH0805R")
      (fields (field (name "MANUFACTURER") "Yageo") (field (name "COMPONENTKIND") "±1%"))
      (libsource (lib "") (part "Resistor_2"))
    )
    (comp (ref "R59")
      (value "4k7")
      (footprint "CH0805R")
      (fields (field (name "MANUFACTURER") "Yageo") (field (name "COMPONENTKIND") "±1%"))
      (libsource (lib "") (part "Resistor_1"))
    )
    (comp (ref "R60")
      (value "4k7")
      (footprint "CH0805R")
      (fields (field (name "MANUFACTURER") "Yageo") (field (name "COMPONENTKIND") "±1%"))
      (libsource (lib "") (part "Resistor_1"))
    )
    (comp (ref "R61")
      (value "4k7")
      (footprint "CH0805R")
      (fields (field (name "MANUFACTURER") "Yageo") (field (name "COMPONENTKIND") "±1%"))
      (libsource (lib "") (part "Resistor_1"))
    )
    (comp (ref "R62")
      (value "4k7")
      (footprint "CH0805R")
      (fields (field (name "MANUFACTURER") "Yageo") (field (name "COMPONENTKIND") "±1%"))
      (libsource (lib "") (part "Resistor_1"))
    )
    (comp (ref "R63")
      (value "10k")
      (footprint "CH0805R")
      (fields (field (name "MANUFACTURER") "Yageo"))
      (libsource (lib "Discrete") (part "Resistor"))
    )
    (comp (ref "R64")
      (value "1k")
      (footprint "CH0805R")
      (fields (field (name "MANUFACTURER") "Yageo") (field (name "COMPONENTKIND") "±1%"))
      (libsource (lib "") (part "Resistor_3"))
    )
    (comp (ref "R65")
      (value "1k")
      (footprint "CH0805R")
      (fields (field (name "MANUFACTURER") "Yageo") (field (name "COMPONENTKIND") "±1%"))
      (libsource (lib "") (part "Resistor_3"))
    )
    (comp (ref "R66")
      (value "1k")
      (footprint "CH0805R")
      (fields (field (name "MANUFACTURER") "Yageo"))
      (libsource (lib "") (part "Resistor_2"))
    )
    (comp (ref "R67")
      (value "100R")
      (footprint "CH0805R")
      (fields (field (name "MANUFACTURER") "Yageo"))
      (libsource (lib "Discrete") (part "Resistor"))
    )
    (comp (ref "R68")
      (value "1k")
      (footprint "CH0805R")
      (fields (field (name "MANUFACTURER") "Yageo"))
      (libsource (lib "") (part "Resistor_2"))
    )
    (comp (ref "R69")
      (value "100R")
      (footprint "CH0805R")
      (fields (field (name "MANUFACTURER") "Yageo"))
      (libsource (lib "Discrete") (part "Resistor"))
    )
    (comp (ref "R70")
      (value "4k7")
      (footprint "CH0805R")
      (fields (field (name "MANUFACTURER") "Yageo") (field (name "COMPONENTKIND") "±1%"))
      (libsource (lib "") (part "Resistor_1"))
    )
    (comp (ref "R71")
      (value "4k7")
      (footprint "CH0805R")
      (fields (field (name "MANUFACTURER") "Yageo") (field (name "COMPONENTKIND") "±1%"))
      (libsource (lib "") (part "Resistor_1"))
    )
    (comp (ref "R72")
      (value "10k")
      (footprint "CH0805R")
      (fields (field (name "MANUFACTURER") "Yageo"))
      (libsource (lib "") (part "Resistor_1"))
    )
    (comp (ref "R73")
      (value "10k")
      (footprint "CH0805R")
      (fields (field (name "MANUFACTURER") "Yageo"))
      (libsource (lib "") (part "Resistor_1"))
    )
    (comp (ref "R74")
      (value "10k")
      (footprint "RES: 3296W")
      (fields (field (name "MANUFACTURER") "Bourns Inc."))
      (libsource (lib "Discrete") (part "ADJ resistor"))
    )
    (comp (ref "R75")
      (value "10k")
      (footprint "RES: 3296W")
      (fields (field (name "MANUFACTURER") "Bourns Inc."))
      (libsource (lib "Discrete") (part "ADJ resistor"))
    )
    (comp (ref "R76")
      (value "10k")
      (footprint "CH0805R")
      (fields (field (name "MANUFACTURER") "Yageo"))
      (libsource (lib "") (part "Resistor_1"))
    )
    (comp (ref "R77")
      (value "10k")
      (footprint "CH0805R")
      (fields (field (name "MANUFACTURER") "Yageo"))
      (libsource (lib "") (part "Resistor_1"))
    )
    (comp (ref "R78")
      (value "4k7")
      (footprint "CH0805R")
      (fields (field (name "MANUFACTURER") "Yageo") (field (name "COMPONENTKIND") "±1%"))
      (libsource (lib "") (part "Resistor_1"))
    )
    (comp (ref "R79")
      (value "10k")
      (footprint "CH0805R")
      (fields (field (name "MANUFACTURER") "Yageo"))
      (libsource (lib "Discrete") (part "Resistor"))
    )
    (comp (ref "R80")
      (value "1k")
      (footprint "CH0805R")
      (fields (field (name "MANUFACTURER") "Yageo"))
      (libsource (lib "Discrete") (part "Resistor"))
    )
    (comp (ref "R81")
      (value "1k")
      (footprint "CH0805R")
      (fields (field (name "MANUFACTURER") "Yageo"))
      (libsource (lib "Discrete") (part "Resistor"))
    )
    (comp (ref "R82")
      (value "1k")
      (footprint "CH0805R")
      (fields (field (name "MANUFACTURER") "Yageo"))
      (libsource (lib "Discrete") (part "Resistor"))
    )
    (comp (ref "R83")
      (value "220k")
      (footprint "CH2512R")
      (fields (field (name "MANUFACTURER") "Yageo"))
      (libsource (lib "") (part "Resistor_2"))
    )
    (comp (ref "T1")
      (value "ETD59/31/22")
      (footprint "TRANS: ETD59/31/22")
      (description "Impulse")
      (fields (field (name "MANUFACTURER") "Epcos"))
      (libsource (lib "Transformers") (part "Push-Pull"))
    )
    (comp (ref "T2")
      (value "ETD59/31/22")
      (footprint "TRANS: ETD59/31/22")
      (description "Impulse")
      (fields (field (name "MANUFACTURER") "Epcos"))
      (libsource (lib "Transformers") (part "Push-Pull"))
    )
    (comp (ref "U1")
      (value "LTV-817S")
      (footprint "4-SMD")
      (fields (field (name "MANUFACTURER") "Lite-On Inc."))
      (libsource (lib "Discrete") (part "Optoisolator"))
    )
    (comp (ref "VD1")
      (value "MMSZ5231B")
      (footprint "SOD123")
      (fields (field (name "MANUFACTURER") "Fairchild/ON Semiconductor"))
      (libsource (lib "Diods") (part "Diod Zener"))
    )
    (comp (ref "VD2")
      (value "SS24FL")
      (footprint "SOD123F")
      (fields (field (name "MANUFACTURER") "Fairchild/ON Semiconductor"))
      (libsource (lib "Diods") (part "Diod Schottky"))
    )
    (comp (ref "VD3")
      (value "SMBJ40A")
      (footprint "SMB")
      (fields (field (name "MANUFACTURER") "Fairchild/ON Semiconductor"))
      (libsource (lib "Diods") (part "Diod Zener"))
    )
    (comp (ref "VD4")
      (value "SMBJ40A")
      (footprint "SMB")
      (fields (field (name "MANUFACTURER") "Fairchild/ON Semiconductor"))
      (libsource (lib "Diods") (part "Diod Zener"))
    )
    (comp (ref "VD5")
      (value "SS24FL")
      (footprint "SOD123F")
      (fields (field (name "MANUFACTURER") "Fairchild/ON Semiconductor"))
      (libsource (lib "Diods") (part "Diod Schottky"))
    )
    (comp (ref "VD6")
      (value "SS24FL")
      (footprint "SOD123F")
      (fields (field (name "MANUFACTURER") "Fairchild/ON Semiconductor"))
      (libsource (lib "Diods") (part "Diod Schottky"))
    )
    (comp (ref "VD7")
      (value "SS24FL")
      (footprint "SOD123F")
      (fields (field (name "MANUFACTURER") "Fairchild/ON Semiconductor"))
      (libsource (lib "Diods") (part "Diod Schottky"))
    )
    (comp (ref "VD8")
      (value "SS24FL")
      (footprint "SOD123F")
      (fields (field (name "MANUFACTURER") "Fairchild/ON Semiconductor"))
      (libsource (lib "Diods") (part "Diod Schottky"))
    )
    (comp (ref "VD9")
      (value "SS24FL")
      (footprint "SOD123F")
      (fields (field (name "MANUFACTURER") "Fairchild/ON Semiconductor"))
      (libsource (lib "Diods") (part "Diod Schottky"))
    )
    (comp (ref "VD10")
      (value "SS24FL")
      (footprint "SOD123F")
      (fields (field (name "MANUFACTURER") "Fairchild/ON Semiconductor"))
      (libsource (lib "Diods") (part "Diod Schottky"))
    )
    (comp (ref "VD11")
      (value "SD15C-01FT")
      (footprint "SOD323")
      (fields (field (name "MANUFACTURER") "Littelfuse Inc."))
      (libsource (lib "Diods") (part "TVS-diod"))
    )
    (comp (ref "VD12")
      (value "SS24FL")
      (footprint "SOD123F")
      (fields (field (name "MANUFACTURER") "Fairchild/ON Semiconductor"))
      (libsource (lib "Diods") (part "Diod Schottky"))
    )
    (comp (ref "VD13")
      (value "SD15C")
      (footprint "SOD323")
      (fields (field (name "MANUFACTURER") "Littelfuse Inc."))
      (libsource (lib "Diods") (part "TVS-diod"))
    )
    (comp (ref "VD14")
      (value "SD15C")
      (footprint "SOD323")
      (fields (field (name "MANUFACTURER") "Littelfuse Inc."))
      (libsource (lib "Diods") (part "TVS-diod"))
    )
    (comp (ref "VD15")
      (value "SD15C")
      (footprint "SOD323")
      (fields (field (name "MANUFACTURER") "Littelfuse Inc."))
      (libsource (lib "Diods") (part "TVS-diod"))
    )
    (comp (ref "VD16")
      (value "SD15C")
      (footprint "SOD323")
      (fields (field (name "MANUFACTURER") "Littelfuse Inc."))
      (libsource (lib "Diods") (part "TVS-diod"))
    )
    (comp (ref "VD17")
      (value "SD15C")
      (footprint "SOD323")
      (fields (field (name "MANUFACTURER") "Littelfuse Inc."))
      (libsource (lib "Diods") (part "TVS-diod"))
    )
    (comp (ref "VD18")
      (value "HFA15TB60PBF")
      (footprint "TO220-2")
      (fields (field (name "MANUFACTURER") "Infineon Technologies"))
      (libsource (lib "Diods") (part "Diod"))
    )
    (comp (ref "VD19")
      (value "HFA15TB60PBF")
      (footprint "TO220-2")
      (fields (field (name "MANUFACTURER") "Infineon Technologies"))
      (libsource (lib "Diods") (part "Diod"))
    )
    (comp (ref "VD20")
      (value "HFA15TB60PBF")
      (footprint "TO220-2")
      (fields (field (name "MANUFACTURER") "Infineon Technologies"))
      (libsource (lib "Diods") (part "Diod"))
    )
    (comp (ref "VD21")
      (value "HFA15TB60PBF")
      (footprint "TO220-2")
      (fields (field (name "MANUFACTURER") "Infineon Technologies"))
      (libsource (lib "Diods") (part "Diod"))
    )
    (comp (ref "VD22")
      (value "TL431AIDBZR")
      (footprint "SOT23_132")
      (fields (field (name "MANUFACTURER") "Texas Instruments"))
      (libsource (lib "Diods") (part "Program Zener"))
    )
    (comp (ref "VD23")
      (value "HFA15TB60PBF")
      (footprint "TO220-2")
      (fields (field (name "MANUFACTURER") "Infineon Technologies"))
      (libsource (lib "Diods") (part "Diod"))
    )
    (comp (ref "VD24")
      (value "HFA15TB60PBF")
      (footprint "TO220-2")
      (fields (field (name "MANUFACTURER") "Infineon Technologies"))
      (libsource (lib "Diods") (part "Diod"))
    )
    (comp (ref "VD25")
      (value "HFA15TB60PBF")
      (footprint "TO220-2")
      (fields (field (name "MANUFACTURER") "Infineon Technologies"))
      (libsource (lib "Diods") (part "Diod"))
    )
    (comp (ref "VD26")
      (value "HFA15TB60PBF")
      (footprint "TO220-2")
      (fields (field (name "MANUFACTURER") "Infineon Technologies"))
      (libsource (lib "Diods") (part "Diod"))
    )
    (comp (ref "VD27")
      (value "SS24FL")
      (footprint "SOD123F")
      (fields (field (name "MANUFACTURER") "Fairchild/ON Semiconductor"))
      (libsource (lib "Diods") (part "Diod Schottky"))
    )
    (comp (ref "VD28")
      (value "SMBJ40A")
      (footprint "SMB")
      (fields (field (name "MANUFACTURER") "Fairchild/ON Semiconductor"))
      (libsource (lib "Diods") (part "Diod Zener"))
    )
    (comp (ref "VD29")
      (value "SMBJ40A")
      (footprint "SMB")
      (fields (field (name "MANUFACTURER") "Fairchild/ON Semiconductor"))
      (libsource (lib "Diods") (part "Diod Zener"))
    )
    (comp (ref "VD30")
      (value "SS24FL")
      (footprint "SOD123F")
      (fields (field (name "MANUFACTURER") "Fairchild/ON Semiconductor"))
      (libsource (lib "Diods") (part "Diod Schottky"))
    )
    (comp (ref "VD31")
      (value "SS24FL")
      (footprint "SOD123F")
      (fields (field (name "MANUFACTURER") "Fairchild/ON Semiconductor"))
      (libsource (lib "Diods") (part "Diod Schottky"))
    )
    (comp (ref "VD32")
      (value "SS24FL")
      (footprint "SOD123F")
      (fields (field (name "MANUFACTURER") "Fairchild/ON Semiconductor"))
      (libsource (lib "Diods") (part "Diod Schottky"))
    )
    (comp (ref "VD33")
      (value "SS24FL")
      (footprint "SOD123F")
      (fields (field (name "MANUFACTURER") "Fairchild/ON Semiconductor"))
      (libsource (lib "Diods") (part "Diod Schottky"))
    )
    (comp (ref "VD34")
      (value "SS24FL")
      (footprint "SOD123F")
      (fields (field (name "MANUFACTURER") "Fairchild/ON Semiconductor"))
      (libsource (lib "Diods") (part "Diod Schottky"))
    )
    (comp (ref "VD35")
      (value "SS24FL")
      (footprint "SOD123F")
      (fields (field (name "MANUFACTURER") "Fairchild/ON Semiconductor"))
      (libsource (lib "Diods") (part "Diod Schottky"))
    )
    (comp (ref "VD36")
      (value "SD15C-01FT")
      (footprint "SOD323")
      (fields (field (name "MANUFACTURER") "Littelfuse Inc."))
      (libsource (lib "Diods") (part "TVS-diod"))
    )
    (comp (ref "VD37")
      (value "SS24FL")
      (footprint "SOD123F")
      (fields (field (name "MANUFACTURER") "Fairchild/ON Semiconductor"))
      (libsource (lib "Diods") (part "Diod Schottky"))
    )
    (comp (ref "VD38")
      (value "SD15C")
      (footprint "SOD323")
      (fields (field (name "MANUFACTURER") "Littelfuse Inc."))
      (libsource (lib "Diods") (part "TVS-diod"))
    )
    (comp (ref "VD39")
      (value "SD15C")
      (footprint "SOD323")
      (fields (field (name "MANUFACTURER") "Littelfuse Inc."))
      (libsource (lib "Diods") (part "TVS-diod"))
    )
    (comp (ref "VD40")
      (value "SD15C")
      (footprint "SOD323")
      (fields (field (name "MANUFACTURER") "Littelfuse Inc."))
      (libsource (lib "Diods") (part "TVS-diod"))
    )
    (comp (ref "VD41")
      (value "SD15C")
      (footprint "SOD323")
      (fields (field (name "MANUFACTURER") "Littelfuse Inc."))
      (libsource (lib "Diods") (part "TVS-diod"))
    )
    (comp (ref "VD42")
      (value "SD15C")
      (footprint "SOD323")
      (fields (field (name "MANUFACTURER") "Littelfuse Inc."))
      (libsource (lib "Diods") (part "TVS-diod"))
    )
    (comp (ref "VD43")
      (value "STPS2L60A")
      (footprint "SMA")
      (fields (field (name "MANUFACTURER") "STMicroelectronics"))
      (libsource (lib "Diods") (part "Diod Schottky"))
    )
    (comp (ref "VD44")
      (value "STPS2L60A")
      (footprint "SMA")
      (fields (field (name "MANUFACTURER") "STMicroelectronics"))
      (libsource (lib "Diods") (part "Diod Schottky"))
    )
    (comp (ref "VD45")
      (value "RED")
      (footprint "CH0805LR")
      (fields (field (name "MANUFACTURER") "Wurth Electronics Inc."))
      (libsource (lib "Discrete") (part "LED"))
    )
    (comp (ref "VD46")
      (value "GREEN")
      (footprint "CH0805LR")
      (fields (field (name "MANUFACTURER") "Wurth Electronics Inc."))
      (libsource (lib "Discrete") (part "LED"))
    )
    (comp (ref "VD47")
      (value "GREEN")
      (footprint "CH0805LR")
      (fields (field (name "MANUFACTURER") "Wurth Electronics Inc."))
      (libsource (lib "Discrete") (part "LED"))
    )
    (comp (ref "VT1")
      (value "IPP083N10N5")
      (footprint "TO220_123")
      (description "Mosfet")
      (fields (field (name "MANUFACTURER") "Infineon Technologies"))
      (libsource (lib "Transistor") (part "N-chanel"))
    )
    (comp (ref "VT2")
      (value "IPP083N10N5")
      (footprint "TO220_123")
      (description "Mosfet")
      (fields (field (name "MANUFACTURER") "Infineon Technologies"))
      (libsource (lib "Transistor") (part "N-chanel"))
    )
    (comp (ref "VT3")
      (value "IPP083N10N5")
      (footprint "TO220_123")
      (description "Mosfet")
      (fields (field (name "MANUFACTURER") "Infineon Technologies"))
      (libsource (lib "Transistor") (part "N-chanel"))
    )
    (comp (ref "VT4")
      (value "IPP083N10N5")
      (footprint "TO220_123")
      (description "Mosfet")
      (fields (field (name "MANUFACTURER") "Infineon Technologies"))
      (libsource (lib "Transistor") (part "N-chanel"))
    )
    (comp (ref "VT5")
      (value "IPP083N10N5")
      (footprint "TO220_123")
      (description "Mosfet")
      (fields (field (name "MANUFACTURER") "Infineon Technologies"))
      (libsource (lib "Transistor") (part "N-chanel"))
    )
    (comp (ref "VT6")
      (value "IPP083N10N5")
      (footprint "TO220_123")
      (description "Mosfet")
      (fields (field (name "MANUFACTURER") "Infineon Technologies"))
      (libsource (lib "Transistor") (part "N-chanel"))
    )
    (comp (ref "VT7")
      (value "IPP083N10N5")
      (footprint "TO220_123")
      (description "Mosfet")
      (fields (field (name "MANUFACTURER") "Infineon Technologies"))
      (libsource (lib "Transistor") (part "N-chanel"))
    )
    (comp (ref "VT8")
      (value "IPP083N10N5")
      (footprint "TO220_123")
      (description "Mosfet")
      (fields (field (name "MANUFACTURER") "Infineon Technologies"))
      (libsource (lib "Transistor") (part "N-chanel"))
    )
    (comp (ref "VT9")
      (value "IPP083N10N5")
      (footprint "TO220_123")
      (description "Mosfet")
      (fields (field (name "MANUFACTURER") "Infineon Technologies"))
      (libsource (lib "Transistor") (part "N-chanel"))
    )
    (comp (ref "VT10")
      (value "IPP083N10N5")
      (footprint "TO220_123")
      (description "Mosfet")
      (fields (field (name "MANUFACTURER") "Infineon Technologies"))
      (libsource (lib "Transistor") (part "N-chanel"))
    )
    (comp (ref "VT11")
      (value "IPP083N10N5")
      (footprint "TO220_123")
      (description "Mosfet")
      (fields (field (name "MANUFACTURER") "Infineon Technologies"))
      (libsource (lib "Transistor") (part "N-chanel"))
    )
    (comp (ref "VT12")
      (value "IPP083N10N5")
      (footprint "TO220_123")
      (description "Mosfet")
      (fields (field (name "MANUFACTURER") "Infineon Technologies"))
      (libsource (lib "Transistor") (part "N-chanel"))
    )
    (comp (ref "VT13")
      (value "BC857BLT1G")
      (footprint "SOT23_132")
      (description "Bipolar")
      (fields (field (name "MANUFACTURER") "ON Semiconductor"))
      (libsource (lib "Transistor") (part "PNP"))
    )
    (comp (ref "VT14")
      (value "IRLML0030TRPBF")
      (footprint "SOT23_123")
      (description "Mosfet")
      (fields (field (name "MANUFACTURER") "Infineon Technologies"))
      (libsource (lib "Transistor") (part "N-chanel"))
    )
    (comp (ref "VT15")
      (value "IRLML0030TRPBF")
      (footprint "SOT23_123")
      (description "Mosfet")
      (fields (field (name "MANUFACTURER") "Infineon Technologies"))
      (libsource (lib "Transistor") (part "N-chanel"))
    )
    (comp (ref "VT16")
      (value "BC857BLT1G")
      (footprint "SOT23_132")
      (description "Bipolar")
      (fields (field (name "MANUFACTURER") "ON Semiconductor"))
      (libsource (lib "Transistor") (part "PNP"))
    )
    (comp (ref "X1")
      (value "\"Вход +24В\"")
      (footprint "CON: 7461383")
      (fields (field (name "MANUFACTURER") "Wurth Electronics Inc."))
      (libsource (lib "Connectors") (part "1-Connector"))
    )
    (comp (ref "X2")
      (value "\"Вход -24В\"")
      (footprint "CON: 7461383")
      (fields (field (name "MANUFACTURER") "Wurth Electronics Inc."))
      (libsource (lib "Connectors") (part "1-Connector"))
    )
    (comp (ref "X3")
      (value "\"Temp №1\"")
      (footprint "CON: WF-02")
      (libsource (lib "") (part "2-Connector_1"))
    )
    (comp (ref "X4")
      (value "\"Вентилятор №1\"")
      (footprint "CON: WF-02")
      (libsource (lib "Connectors") (part "2-Connector"))
    )
    (comp (ref "X5")
      (value "\"Temp №2\"")
      (footprint "CON: WF-02")
      (libsource (lib "") (part "2-Connector_1"))
    )
    (comp (ref "X6")
      (value "\"Вентилятор №2\"")
      (footprint "CON: WF-02")
      (libsource (lib "Connectors") (part "2-Connector"))
    )
    (comp (ref "X7")
      (value "\"Выход 380В\"")
      (footprint "CON: X977B02")
      (fields (field (name "MANUFACTURER") "Ningbo"))
      (libsource (lib "Connectors") (part "2-Connector"))
    )
  )
  (nets
    (net (code "1") (name "/PWM_CH1") (class "Default")
      (node (ref "D14") (pin "8") (pinfunction "OUT1_8") (pintype "passive"))
      (node (ref "R22") (pin "2") (pinfunction "2_2") (pintype "passive"))
    )
    (net (code "2") (name "/PWM_CH2") (class "Default")
      (node (ref "D14") (pin "9") (pinfunction "OUT2_9") (pintype "passive"))
      (node (ref "R49") (pin "2") (pinfunction "2_2") (pintype "passive"))
    )
    (net (code "3") (name "/PWM_EN") (class "Default")
      (node (ref "R12") (pin "2") (pinfunction "2_2") (pintype "passive"))
      (node (ref "R3") (pin "1") (pinfunction "1_1") (pintype "passive"))
      (node (ref "R41") (pin "2") (pinfunction "2_2") (pintype "passive"))
      (node (ref "R63") (pin "2") (pinfunction "2_2") (pintype "passive"))
      (node (ref "R79") (pin "2") (pinfunction "2_2") (pintype "passive"))
      (node (ref "VT13") (pin "1") (pinfunction "B_1") (pintype "passive"))
      (node (ref "VT16") (pin "1") (pinfunction "B_1") (pintype "passive"))
    )
    (net (code "4") (name "GND") (class "Default")
      (node (ref "C10") (pin "2") (pinfunction "2_2") (pintype "power_in"))
      (node (ref "C11") (pin "2") (pinfunction "2_2") (pintype "power_in"))
      (node (ref "C12") (pin "2") (pinfunction "2_2") (pintype "power_in"))
      (node (ref "C13") (pin "2") (pinfunction "2_2") (pintype "power_in"))
      (node (ref "C14") (pin "2") (pinfunction "2_2") (pintype "power_in"))
      (node (ref "C15") (pin "2") (pinfunction "2_2") (pintype "power_in"))
      (node (ref "C16") (pin "2") (pinfunction "2_2") (pintype "power_in"))
      (node (ref "C17") (pin "2") (pinfunction "2_2") (pintype "power_in"))
      (node (ref "C18") (pin "1") (pinfunction "1_1") (pintype "power_in"))
      (node (ref "C19") (pin "2") (pinfunction "2_2") (pintype "power_in"))
      (node (ref "C2") (pin "2") (pinfunction "2_2") (pintype "power_in"))
      (node (ref "C20") (pin "1") (pinfunction "1_1") (pintype "power_in"))
      (node (ref "C21") (pin "2") (pinfunction "2_2") (pintype "power_in"))
      (node (ref "C22") (pin "1") (pinfunction "1_1") (pintype "power_in"))
      (node (ref "C23") (pin "1") (pinfunction "1_1") (pintype "power_in"))
      (node (ref "C24") (pin "1") (pinfunction "1_1") (pintype "power_in"))
      (node (ref "C25") (pin "1") (pinfunction "1_1") (pintype "power_in"))
      (node (ref "C26") (pin "2") (pinfunction "2_2") (pintype "power_in"))
      (node (ref "C27") (pin "2") (pinfunction "2_2") (pintype "power_in"))
      (node (ref "C3") (pin "2") (pinfunction "2_2") (pintype "power_in"))
      (node (ref "C34") (pin "2") (pinfunction "2_2") (pintype "power_in"))
      (node (ref "C35") (pin "1") (pinfunction "1_1") (pintype "power_in"))
      (node (ref "C36") (pin "2") (pinfunction "2_2") (pintype "power_in"))
      (node (ref "C37") (pin "1") (pinfunction "1_1") (pintype "power_in"))
      (node (ref "C38") (pin "1") (pinfunction "1_1") (pintype "power_in"))
      (node (ref "C39") (pin "1") (pinfunction "1_1") (pintype "power_in"))
      (node (ref "C4") (pin "2") (pinfunction "2_2") (pintype "power_in"))
      (node (ref "C40") (pin "1") (pinfunction "1_1") (pintype "power_in"))
      (node (ref "C41") (pin "2") (pinfunction "2_2") (pintype "power_in"))
      (node (ref "C42") (pin "2") (pinfunction "2_2") (pintype "power_in"))
      (node (ref "C43") (pin "2") (pinfunction "2_2") (pintype "power_in"))
      (node (ref "C44") (pin "1") (pinfunction "1_1") (pintype "power_in"))
      (node (ref "C45") (pin "1") (pinfunction "1_1") (pintype "power_in"))
      (node (ref "C46") (pin "2") (pinfunction "2_2") (pintype "power_in"))
      (node (ref "C47") (pin "1") (pinfunction "1_1") (pintype "power_in"))
      (node (ref "C48") (pin "1") (pinfunction "1_1") (pintype "power_in"))
      (node (ref "C49") (pin "1") (pinfunction "1_1") (pintype "power_in"))
      (node (ref "C5") (pin "2") (pinfunction "2_2") (pintype "power_in"))
      (node (ref "C50") (pin "1") (pinfunction "1_1") (pintype "power_in"))
      (node (ref "C51") (pin "1") (pinfunction "1_1") (pintype "power_in"))
      (node (ref "C52") (pin "1") (pinfunction "1_1") (pintype "power_in"))
      (node (ref "C54") (pin "1") (pinfunction "1_1") (pintype "power_in"))
      (node (ref "C55") (pin "1") (pinfunction "1_1") (pintype "power_in"))
      (node (ref "C57") (pin "1") (pinfunction "1_1") (pintype "power_in"))
      (node (ref "C58") (pin "1") (pinfunction "1_1") (pintype "power_in"))
      (node (ref "C59") (pin "1") (pinfunction "1_1") (pintype "power_in"))
      (node (ref "C6") (pin "2") (pinfunction "2_2") (pintype "power_in"))
      (node (ref "C60") (pin "1") (pinfunction "1_1") (pintype "power_in"))
      (node (ref "C62") (pin "1") (pinfunction "1_1") (pintype "power_in"))
      (node (ref "C63") (pin "1") (pinfunction "1_1") (pintype "power_in"))
      (node (ref "C65") (pin "1") (pinfunction "1_1") (pintype "power_in"))
      (node (ref "C66") (pin "1") (pinfunction "1_1") (pintype "power_in"))
      (node (ref "C67") (pin "1") (pinfunction "1_1") (pintype "power_in"))
      (node (ref "C68") (pin "1") (pinfunction "1_1") (pintype "power_in"))
      (node (ref "C69") (pin "1") (pinfunction "1_1") (pintype "power_in"))
      (node (ref "C7") (pin "2") (pinfunction "2_2") (pintype "power_in"))
      (node (ref "C70") (pin "1") (pinfunction "1_1") (pintype "power_in"))
      (node (ref "C8") (pin "2") (pinfunction "2_2") (pintype "power_in"))
      (node (ref "C9") (pin "2") (pinfunction "2_2") (pintype "power_in"))
      (node (ref "D1") (pin "2") (pinfunction "VSS_2") (pintype "power_in"))
      (node (ref "D10") (pin "3") (pinfunction "EN_3") (pintype "passive"))
      (node (ref "D10") (pin "7") (pinfunction "GND_7") (pintype "passive"))
      (node (ref "D11") (pin "3") (pinfunction "EN_3") (pintype "passive"))
      (node (ref "D11") (pin "7") (pinfunction "GND_7") (pintype "passive"))
      (node (ref "D12") (pin "1") (pinfunction "GND_1") (pintype "passive"))
      (node (ref "D13") (pin "2") (pinfunction "GND_2") (pintype "power_in"))
      (node (ref "D14") (pin "1") (pinfunction "IN1+_1") (pintype "passive"))
      (node (ref "D14") (pin "10") (pinfunction "GND_10") (pintype "passive"))
      (node (ref "D14") (pin "16") (pinfunction "IN2+_16") (pintype "passive"))
      (node (ref "D14") (pin "7") (pinfunction "GND_7") (pintype "passive"))
      (node (ref "D15") (pin "2") (pinfunction "VSS_2") (pintype "power_in"))
      (node (ref "D16") (pin "2") (pinfunction "VSS_2") (pintype "power_in"))
      (node (ref "D2") (pin "2") (pinfunction "VSS_2") (pintype "power_in"))
      (node (ref "D3") (pin "2") (pinfunction "GND_2") (pintype "power_in"))
      (node (ref "D4") (pin "4") (pinfunction "COM_4") (pintype "power_in"))
      (node (ref "D5") (pin "4") (pinfunction "AGND_4") (pintype "passive"))
      (node (ref "D5") (pin "5") (pinfunction "PGND_5") (pintype "passive"))
      (node (ref "D6") (pin "2") (pinfunction "VSS_2") (pintype "power_in"))
      (node (ref "D7") (pin "2") (pinfunction "GND_2") (pintype "power_in"))
      (node (ref "D8") (pin "4") (pinfunction "COM_4") (pintype "power_in"))
      (node (ref "D9") (pin "4") (pinfunction "AGND_4") (pintype "passive"))
      (node (ref "D9") (pin "5") (pinfunction "PGND_5") (pintype "passive"))
      (node (ref "R10") (pin "2") (pinfunction "2_2") (pintype "passive"))
      (node (ref "R11") (pin "2") (pinfunction "2_2") (pintype "passive"))
      (node (ref "R25") (pin "1") (pinfunction "1_1") (pintype "passive"))
      (node (ref "R26") (pin "1") (pinfunction "1_1") (pintype "passive"))
      (node (ref "R27") (pin "1") (pinfunction "1_1") (pintype "passive"))
      (node (ref "R28") (pin "1") (pinfunction "1_1") (pintype "passive"))
      (node (ref "R29") (pin "1") (pinfunction "1_1") (pintype "passive"))
      (node (ref "R30") (pin "1") (pinfunction "1_1") (pintype "passive"))
      (node (ref "R31") (pin "1") (pinfunction "1_1") (pintype "passive"))
      (node (ref "R39") (pin "2") (pinfunction "2_2") (pintype "passive"))
      (node (ref "R4") (pin "2") (pinfunction "2_2") (pintype "passive"))
      (node (ref "R40") (pin "2") (pinfunction "2_2") (pintype "passive"))
      (node (ref "R5") (pin "2") (pinfunction "2_2") (pintype "passive"))
      (node (ref "R50") (pin "1") (pinfunction "1_1") (pintype "passive"))
      (node (ref "R51") (pin "1") (pinfunction "1_1") (pintype "passive"))
      (node (ref "R52") (pin "1") (pinfunction "1_1") (pintype "passive"))
      (node (ref "R53") (pin "1") (pinfunction "1_1") (pintype "passive"))
      (node (ref "R54") (pin "1") (pinfunction "1_1") (pintype "passive"))
      (node (ref "R55") (pin "1") (pinfunction "1_1") (pintype "passive"))
      (node (ref "R56") (pin "1") (pinfunction "1_1") (pintype "passive"))
      (node (ref "R59") (pin "1") (pinfunction "1_1") (pintype "passive"))
      (node (ref "R60") (pin "1") (pinfunction "1_1") (pintype "passive"))
      (node (ref "R61") (pin "1") (pinfunction "1_1") (pintype "passive"))
      (node (ref "R62") (pin "1") (pinfunction "1_1") (pintype "passive"))
      (node (ref "R70") (pin "1") (pinfunction "1_1") (pintype "passive"))
      (node (ref "R71") (pin "1") (pinfunction "1_1") (pintype "passive"))
      (node (ref "R72") (pin "1") (pinfunction "1_1") (pintype "passive"))
      (node (ref "R73") (pin "1") (pinfunction "1_1") (pintype "passive"))
      (node (ref "R74") (pin "1") (pinfunction "1_1") (pintype "passive"))
      (node (ref "R74") (pin "2") (pinfunction "2_2") (pintype "passive"))
      (node (ref "R75") (pin "1") (pinfunction "1_1") (pintype "passive"))
      (node (ref "R75") (pin "2") (pinfunction "2_2") (pintype "passive"))
      (node (ref "R76") (pin "1") (pinfunction "1_1") (pintype "passive"))
      (node (ref "R77") (pin "1") (pinfunction "1_1") (pintype "passive"))
      (node (ref "R78") (pin "1") (pinfunction "1_1") (pintype "passive"))
      (node (ref "R80") (pin "2") (pinfunction "2_2") (pintype "passive"))
      (node (ref "R81") (pin "2") (pinfunction "2_2") (pintype "passive"))
      (node (ref "R82") (pin "2") (pinfunction "2_2") (pintype "passive"))
      (node (ref "VD1") (pin "1") (pinfunction "A_1") (pintype "passive"))
      (node (ref "VD11") (pin "1") (pinfunction "A_1") (pintype "passive"))
      (node (ref "VD12") (pin "1") (pinfunction "1_1") (pintype "passive"))
      (node (ref "VD13") (pin "1") (pinfunction "A_1") (pintype "passive"))
      (node (ref "VD14") (pin "1") (pinfunction "A_1") (pintype "passive"))
      (node (ref "VD15") (pin "1") (pinfunction "A_1") (pintype "passive"))
      (node (ref "VD16") (pin "1") (pinfunction "A_1") (pintype "passive"))
      (node (ref "VD17") (pin "1") (pinfunction "A_1") (pintype "passive"))
      (node (ref "VD28") (pin "1") (pinfunction "A_1") (pintype "passive"))
      (node (ref "VD29") (pin "1") (pinfunction "A_1") (pintype "passive"))
      (node (ref "VD3") (pin "1") (pinfunction "A_1") (pintype "passive"))
      (node (ref "VD36") (pin "1") (pinfunction "A_1") (pintype "passive"))
      (node (ref "VD37") (pin "1") (pinfunction "1_1") (pintype "passive"))
      (node (ref "VD38") (pin "1") (pinfunction "A_1") (pintype "passive"))
      (node (ref "VD39") (pin "1") (pinfunction "A_1") (pintype "passive"))
      (node (ref "VD4") (pin "1") (pinfunction "A_1") (pintype "passive"))
      (node (ref "VD40") (pin "1") (pinfunction "A_1") (pintype "passive"))
      (node (ref "VD41") (pin "1") (pinfunction "A_1") (pintype "passive"))
      (node (ref "VD42") (pin "1") (pinfunction "A_1") (pintype "passive"))
      (node (ref "VD43") (pin "1") (pinfunction "1_1") (pintype "passive"))
      (node (ref "VD44") (pin "1") (pinfunction "1_1") (pintype "passive"))
      (node (ref "VT1") (pin "3") (pinfunction "S_3") (pintype "passive"))
      (node (ref "VT10") (pin "3") (pinfunction "S_3") (pintype "passive"))
      (node (ref "VT11") (pin "3") (pinfunction "S_3") (pintype "passive"))
      (node (ref "VT12") (pin "3") (pinfunction "S_3") (pintype "passive"))
      (node (ref "VT14") (pin "3") (pinfunction "S_3") (pintype "passive"))
      (node (ref "VT15") (pin "3") (pinfunction "S_3") (pintype "passive"))
      (node (ref "VT2") (pin "3") (pinfunction "S_3") (pintype "passive"))
      (node (ref "VT3") (pin "3") (pinfunction "S_3") (pintype "passive"))
      (node (ref "VT4") (pin "3") (pinfunction "S_3") (pintype "passive"))
      (node (ref "VT5") (pin "3") (pinfunction "S_3") (pintype "passive"))
      (node (ref "VT6") (pin "3") (pinfunction "S_3") (pintype "passive"))
      (node (ref "VT7") (pin "3") (pinfunction "S_3") (pintype "passive"))
      (node (ref "VT8") (pin "3") (pinfunction "S_3") (pintype "passive"))
      (node (ref "VT9") (pin "3") (pinfunction "S_3") (pintype "passive"))
      (node (ref "X2") (pin "1") (pinfunction "1_1") (pintype "passive"))
    )
    (net (code "5") (name "GND2") (class "Default")
      (node (ref "C30") (pin "2") (pinfunction "2_2") (pintype "power_in"))
      (node (ref "C31") (pin "2") (pinfunction "2_2") (pintype "power_in"))
      (node (ref "C32") (pin "2") (pinfunction "2_2") (pintype "power_in"))
      (node (ref "C33") (pin "2") (pinfunction "2_2") (pintype "power_in"))
      (node (ref "C61") (pin "1") (pinfunction "1_1") (pintype "power_in"))
      (node (ref "C63") (pin "2") (pinfunction "2_2") (pintype "power_in"))
      (node (ref "D13") (pin "4") (pinfunction "GND2_4") (pintype "power_in"))
      (node (ref "R36") (pin "2") (pinfunction "2_2") (pintype "passive"))
      (node (ref "R37") (pin "1") (pinfunction "1_1") (pintype "passive"))
      (node (ref "R37") (pin "2") (pinfunction "2_2") (pintype "passive"))
      (node (ref "R83") (pin "2") (pinfunction "2_2") (pintype "passive"))
      (node (ref "VD22") (pin "3") (pinfunction "3_3") (pintype "power_in"))
      (node (ref "VD23") (pin "1") (pinfunction "1_1") (pintype "passive"))
      (node (ref "VD24") (pin "1") (pinfunction "1_1") (pintype "passive"))
      (node (ref "VD25") (pin "1") (pinfunction "1_1") (pintype "passive"))
      (node (ref "VD26") (pin "1") (pinfunction "1_1") (pintype "passive"))
      (node (ref "X7") (pin "2") (pinfunction "2_2") (pintype "passive"))
    )
    (net (code "6") (name "Net-(C28-Pad1)") (class "Default")
      (node (ref "C28") (pin "1") (pinfunction "1_1") (pintype "power_in"))
      (node (ref "C29") (pin "1") (pinfunction "1_1") (pintype "power_in"))
      (node (ref "R23") (pin "2") (pinfunction "2_2") (pintype "passive"))
      (node (ref "R36") (pin "1") (pinfunction "1_1") (pintype "passive"))
      (node (ref "R37") (pin "3") (pinfunction "3_3") (pintype "passive"))
      (node (ref "VD22") (pin "2") (pinfunction "2_2") (pintype "power_in"))
    )
    (net (code "7") (name "Net-(C28-Pad2)") (class "Default")
      (node (ref "C28") (pin "2") (pinfunction "2_2") (pintype "power_in"))
      (node (ref "R32") (pin "2") (pinfunction "2_2") (pintype "passive"))
    )
    (net (code "8") (name "Net-(C46-Pad1)") (class "Default")
      (node (ref "C46") (pin "1") (pinfunction "1_1") (pintype "power_in"))
      (node (ref "C47") (pin "2") (pinfunction "2_2") (pintype "power_in"))
      (node (ref "C48") (pin "2") (pinfunction "2_2") (pintype "power_in"))
      (node (ref "FB1") (pin "2") (pinfunction "2_2") (pintype "passive"))
      (node (ref "L3") (pin "1") (pinfunction "1_1") (pintype "passive"))
      (node (ref "R58") (pin "1") (pinfunction "1_1") (pintype "passive"))
    )
    (net (code "9") (name "Net-(C53-Pad1)") (class "Default")
      (node (ref "C53") (pin "1") (pinfunction "1_1") (pintype "power_in"))
      (node (ref "R60") (pin "2") (pinfunction "2_2") (pintype "passive"))
    )
    (net (code "10") (name "Net-(C56-Pad1)") (class "Default")
      (node (ref "C56") (pin "1") (pinfunction "1_1") (pintype "power_in"))
      (node (ref "R61") (pin "2") (pinfunction "2_2") (pintype "passive"))
    )
    (net (code "11") (name "Net-(C65-Pad2)") (class "Default")
      (node (ref "C65") (pin "2") (pinfunction "2_2") (pintype "power_in"))
      (node (ref "R66") (pin "2") (pinfunction "2_2") (pintype "passive"))
      (node (ref "R70") (pin "2") (pinfunction "2_2") (pintype "passive"))
      (node (ref "X3") (pin "2") (pinfunction "2_2") (pintype "passive"))
    )
    (net (code "12") (name "Net-(C66-Pad2)") (class "Default")
      (node (ref "C66") (pin "2") (pinfunction "2_2") (pintype "power_in"))
      (node (ref "R68") (pin "2") (pinfunction "2_2") (pintype "passive"))
      (node (ref "R71") (pin "2") (pinfunction "2_2") (pintype "passive"))
      (node (ref "X5") (pin "2") (pinfunction "2_2") (pintype "passive"))
    )
    (net (code "13") (name "Net-(D1-IN+)") (class "Default")
      (node (ref "C1") (pin "2") (pinfunction "2_2") (pintype "power_in"))
      (node (ref "D1") (pin "3") (pinfunction "IN+_3") (pintype "input"))
      (node (ref "R2") (pin "2") (pinfunction "2_2") (pintype "passive"))
      (node (ref "R4") (pin "1") (pinfunction "1_1") (pintype "passive"))
      (node (ref "VD1") (pin "2") (pinfunction "C_2") (pintype "passive"))
    )
    (net (code "14") (name "Net-(D1-IN-)") (class "Default")
      (node (ref "D1") (pin "4") (pinfunction "IN-_4") (pintype "input"))
      (node (ref "R1") (pin "1") (pinfunction "1_1") (pintype "passive"))
      (node (ref "R5") (pin "1") (pinfunction "1_1") (pintype "passive"))
    )
    (net (code "15") (name "Net-(D1-OUT)") (class "Default")
      (node (ref "D1") (pin "1") (pinfunction "OUT_1") (pintype "output"))
      (node (ref "R3") (pin "2") (pinfunction "2_2") (pintype "passive"))
    )
    (net (code "16") (name "Net-(D2-IN+)") (class "Default")
      (node (ref "D2") (pin "3") (pinfunction "IN+_3") (pintype "input"))
      (node (ref "R11") (pin "1") (pinfunction "1_1") (pintype "passive"))
      (node (ref "R6") (pin "1") (pinfunction "1_1") (pintype "passive"))
    )
    (net (code "17") (name "Net-(D2-IN-)") (class "Default")
      (node (ref "C21") (pin "1") (pinfunction "1_1") (pintype "power_in"))
      (node (ref "D2") (pin "4") (pinfunction "IN-_4") (pintype "input"))
      (node (ref "R7") (pin "2") (pinfunction "2_2") (pintype "passive"))
    )
    (net (code "18") (name "Net-(D2-OUT)") (class "Default")
      (node (ref "D2") (pin "1") (pinfunction "OUT_1") (pintype "output"))
      (node (ref "R12") (pin "1") (pinfunction "1_1") (pintype "passive"))
      (node (ref "R13") (pin "2") (pinfunction "2_2") (pintype "passive"))
    )
    (net (code "19") (name "Net-(D3-IN+)") (class "Default")
      (node (ref "C19") (pin "1") (pinfunction "1_1") (pintype "power_in"))
      (node (ref "D3") (pin "3") (pinfunction "IN+_3") (pintype "input"))
      (node (ref "R9") (pin "2") (pinfunction "2_2") (pintype "passive"))
    )
    (net (code "20") (name "Net-(D3-IN-)") (class "Default")
      (node (ref "D3") (pin "4") (pinfunction "IN-_4") (pintype "input"))
      (node (ref "R10") (pin "1") (pinfunction "1_1") (pintype "passive"))
      (node (ref "R8") (pin "1") (pinfunction "1_1") (pintype "passive"))
    )
    (net (code "21") (name "Net-(D3-OUT)") (class "Default")
      (node (ref "D3") (pin "1") (pinfunction "OUT_1") (pintype "output"))
      (node (ref "R7") (pin "1") (pinfunction "1_1") (pintype "passive"))
      (node (ref "R8") (pin "2") (pinfunction "2_2") (pintype "passive"))
    )
    (net (code "22") (name "Net-(D4-CS)") (class "Default")
      (node (ref "D4") (pin "1") (pinfunction "CS_1") (pintype "output"))
      (node (ref "R9") (pin "1") (pinfunction "1_1") (pintype "passive"))
    )
    (net (code "23") (name "Net-(D4-GATE)") (class "Default")
      (node (ref "D4") (pin "3") (pinfunction "GATE_3") (pintype "input"))
      (node (ref "R16") (pin "1") (pinfunction "1_1") (pintype "passive"))
      (node (ref "R26") (pin "2") (pinfunction "2_2") (pintype "passive"))
      (node (ref "VD11") (pin "2") (pinfunction "C_2") (pintype "passive"))
      (node (ref "VD5") (pin "1") (pinfunction "1_1") (pintype "passive"))
      (node (ref "VT1") (pin "1") (pinfunction "G_1") (pintype "passive"))
    )
    (net (code "24") (name "Net-(D4-VS)") (class "Default")
      (node (ref "D4") (pin "5") (pinfunction "VS_5") (pintype "power_in"))
      (node (ref "T1") (pin "1") (pinfunction "1_1") (pintype "power_in"))
      (node (ref "T2") (pin "1") (pinfunction "1_1") (pintype "power_in"))
      (node (ref "VD3") (pin "2") (pinfunction "C_2") (pintype "passive"))
      (node (ref "VD4") (pin "2") (pinfunction "C_2") (pintype "passive"))
      (node (ref "VT1") (pin "2") (pinfunction "D_2") (pintype "passive"))
      (node (ref "VT2") (pin "2") (pinfunction "D_2") (pintype "passive"))
      (node (ref "VT3") (pin "2") (pinfunction "D_2") (pintype "passive"))
      (node (ref "VT4") (pin "2") (pinfunction "D_2") (pintype "passive"))
      (node (ref "VT5") (pin "2") (pinfunction "D_2") (pintype "passive"))
      (node (ref "VT6") (pin "2") (pinfunction "D_2") (pintype "passive"))
    )
    (net (code "25") (name "Net-(D5-EN)") (class "Default")
      (node (ref "D5") (pin "3") (pinfunction "EN_3") (pintype "input"))
      (node (ref "R13") (pin "1") (pinfunction "1_1") (pintype "passive"))
    )
    (net (code "26") (name "Net-(D5-IN)") (class "Default")
      (node (ref "C23") (pin "2") (pinfunction "2_2") (pintype "power_in"))
      (node (ref "D5") (pin "2") (pinfunction "IN_2") (pintype "input"))
      (node (ref "R22") (pin "1") (pinfunction "1_1") (pintype "passive"))
      (node (ref "R25") (pin "2") (pinfunction "2_2") (pintype "passive"))
    )
    (net (code "27") (name "Net-(D5-OUT-Pad6)") (class "Default")
      (node (ref "D5") (pin "6") (pinfunction "OUT_6") (pintype "output"))
      (node (ref "D5") (pin "7") (pinfunction "OUT_7") (pintype "output"))
      (node (ref "R16") (pin "2") (pinfunction "2_2") (pintype "passive"))
      (node (ref "R17") (pin "2") (pinfunction "2_2") (pintype "passive"))
      (node (ref "R18") (pin "2") (pinfunction "2_2") (pintype "passive"))
      (node (ref "R19") (pin "2") (pinfunction "2_2") (pintype "passive"))
      (node (ref "R20") (pin "2") (pinfunction "2_2") (pintype "passive"))
      (node (ref "R21") (pin "2") (pinfunction "2_2") (pintype "passive"))
      (node (ref "VD10") (pin "2") (pinfunction "2_2") (pintype "passive"))
      (node (ref "VD12") (pin "2") (pinfunction "2_2") (pintype "passive"))
      (node (ref "VD2") (pin "1") (pinfunction "1_1") (pintype "passive"))
      (node (ref "VD5") (pin "2") (pinfunction "2_2") (pintype "passive"))
      (node (ref "VD6") (pin "2") (pinfunction "2_2") (pintype "passive"))
      (node (ref "VD7") (pin "2") (pinfunction "2_2") (pintype "passive"))
      (node (ref "VD8") (pin "2") (pinfunction "2_2") (pintype "passive"))
      (node (ref "VD9") (pin "2") (pinfunction "2_2") (pintype "passive"))
    )
    (net (code "28") (name "Net-(D6-IN+)") (class "Default")
      (node (ref "D6") (pin "3") (pinfunction "IN+_3") (pintype "input"))
      (node (ref "R33") (pin "1") (pinfunction "1_1") (pintype "passive"))
      (node (ref "R40") (pin "1") (pinfunction "1_1") (pintype "passive"))
    )
    (net (code "29") (name "Net-(D6-IN-)") (class "Default")
      (node (ref "C36") (pin "1") (pinfunction "1_1") (pintype "power_in"))
      (node (ref "D6") (pin "4") (pinfunction "IN-_4") (pintype "input"))
      (node (ref "R34") (pin "2") (pinfunction "2_2") (pintype "passive"))
    )
    (net (code "30") (name "Net-(D6-OUT)") (class "Default")
      (node (ref "D6") (pin "1") (pinfunction "OUT_1") (pintype "output"))
      (node (ref "R41") (pin "1") (pinfunction "1_1") (pintype "passive"))
      (node (ref "R42") (pin "2") (pinfunction "2_2") (pintype "passive"))
    )
    (net (code "31") (name "Net-(D7-IN+)") (class "Default")
      (node (ref "C34") (pin "1") (pinfunction "1_1") (pintype "power_in"))
      (node (ref "D7") (pin "3") (pinfunction "IN+_3") (pintype "input"))
      (node (ref "R38") (pin "2") (pinfunction "2_2") (pintype "passive"))
    )
    (net (code "32") (name "Net-(D7-IN-)") (class "Default")
      (node (ref "D7") (pin "4") (pinfunction "IN-_4") (pintype "input"))
      (node (ref "R35") (pin "1") (pinfunction "1_1") (pintype "passive"))
      (node (ref "R39") (pin "1") (pinfunction "1_1") (pintype "passive"))
    )
    (net (code "33") (name "Net-(D7-OUT)") (class "Default")
      (node (ref "D7") (pin "1") (pinfunction "OUT_1") (pintype "output"))
      (node (ref "R34") (pin "1") (pinfunction "1_1") (pintype "passive"))
      (node (ref "R35") (pin "2") (pinfunction "2_2") (pintype "passive"))
    )
    (net (code "34") (name "Net-(D8-CS)") (class "Default")
      (node (ref "D8") (pin "1") (pinfunction "CS_1") (pintype "output"))
      (node (ref "R38") (pin "1") (pinfunction "1_1") (pintype "passive"))
    )
    (net (code "35") (name "Net-(D8-GATE)") (class "Default")
      (node (ref "D8") (pin "3") (pinfunction "GATE_3") (pintype "input"))
      (node (ref "R43") (pin "1") (pinfunction "1_1") (pintype "passive"))
      (node (ref "R51") (pin "2") (pinfunction "2_2") (pintype "passive"))
      (node (ref "VD30") (pin "1") (pinfunction "1_1") (pintype "passive"))
      (node (ref "VD36") (pin "2") (pinfunction "C_2") (pintype "passive"))
      (node (ref "VT7") (pin "1") (pinfunction "G_1") (pintype "passive"))
    )
    (net (code "36") (name "Net-(D8-VS)") (class "Default")
      (node (ref "D8") (pin "5") (pinfunction "VS_5") (pintype "power_in"))
      (node (ref "T1") (pin "3") (pinfunction "3_3") (pintype "power_in"))
      (node (ref "T2") (pin "3") (pinfunction "3_3") (pintype "power_in"))
      (node (ref "VD28") (pin "2") (pinfunction "C_2") (pintype "passive"))
      (node (ref "VD29") (pin "2") (pinfunction "C_2") (pintype "passive"))
      (node (ref "VT10") (pin "2") (pinfunction "D_2") (pintype "passive"))
      (node (ref "VT11") (pin "2") (pinfunction "D_2") (pintype "passive"))
      (node (ref "VT12") (pin "2") (pinfunction "D_2") (pintype "passive"))
      (node (ref "VT7") (pin "2") (pinfunction "D_2") (pintype "passive"))
      (node (ref "VT8") (pin "2") (pinfunction "D_2") (pintype "passive"))
      (node (ref "VT9") (pin "2") (pinfunction "D_2") (pintype "passive"))
    )
    (net (code "37") (name "Net-(D9-EN)") (class "Default")
      (node (ref "D9") (pin "3") (pinfunction "EN_3") (pintype "input"))
      (node (ref "R42") (pin "1") (pinfunction "1_1") (pintype "passive"))
    )
    (net (code "38") (name "Net-(D9-IN)") (class "Default")
      (node (ref "C38") (pin "2") (pinfunction "2_2") (pintype "power_in"))
      (node (ref "D9") (pin "2") (pinfunction "IN_2") (pintype "input"))
      (node (ref "R49") (pin "1") (pinfunction "1_1") (pintype "passive"))
      (node (ref "R50") (pin "2") (pinfunction "2_2") (pintype "passive"))
    )
    (net (code "39") (name "Net-(D9-OUT-Pad6)") (class "Default")
      (node (ref "D9") (pin "6") (pinfunction "OUT_6") (pintype "output"))
      (node (ref "D9") (pin "7") (pinfunction "OUT_7") (pintype "output"))
      (node (ref "R43") (pin "2") (pinfunction "2_2") (pintype "passive"))
      (node (ref "R44") (pin "2") (pinfunction "2_2") (pintype "passive"))
      (node (ref "R45") (pin "2") (pinfunction "2_2") (pintype "passive"))
      (node (ref "R46") (pin "2") (pinfunction "2_2") (pintype "passive"))
      (node (ref "R47") (pin "2") (pinfunction "2_2") (pintype "passive"))
      (node (ref "R48") (pin "2") (pinfunction "2_2") (pintype "passive"))
      (node (ref "VD27") (pin "1") (pinfunction "1_1") (pintype "passive"))
      (node (ref "VD30") (pin "2") (pinfunction "2_2") (pintype "passive"))
      (node (ref "VD31") (pin "2") (pinfunction "2_2") (pintype "passive"))
      (node (ref "VD32") (pin "2") (pinfunction "2_2") (pintype "passive"))
      (node (ref "VD33") (pin "2") (pinfunction "2_2") (pintype "passive"))
      (node (ref "VD34") (pin "2") (pinfunction "2_2") (pintype "passive"))
      (node (ref "VD35") (pin "2") (pinfunction "2_2") (pintype "passive"))
      (node (ref "VD37") (pin "2") (pinfunction "2_2") (pintype "passive"))
    )
    (net (code "40") (name "Net-(D10-COMP)") (class "Default")
      (node (ref "C53") (pin "2") (pinfunction "2_2") (pintype "power_in"))
      (node (ref "C57") (pin "2") (pinfunction "2_2") (pintype "power_in"))
      (node (ref "D10") (pin "4") (pinfunction "COMP_4") (pintype "passive"))
    )
    (net (code "41") (name "Net-(D10-FB)") (class "Default")
      (node (ref "C59") (pin "2") (pinfunction "2_2") (pintype "power_in"))
      (node (ref "D10") (pin "5") (pinfunction "FB_5") (pintype "passive"))
      (node (ref "R57") (pin "2") (pinfunction "2_2") (pintype "passive"))
      (node (ref "R59") (pin "2") (pinfunction "2_2") (pintype "passive"))
    )
    (net (code "42") (name "Net-(D10-OUT)") (class "Default")
      (node (ref "D10") (pin "1") (pinfunction "OUT_1") (pintype "passive"))
      (node (ref "L2") (pin "2") (pinfunction "2_2") (pintype "passive"))
      (node (ref "VD43") (pin "2") (pinfunction "2_2") (pintype "passive"))
    )
    (net (code "43") (name "Net-(D11-COMP)") (class "Default")
      (node (ref "C56") (pin "2") (pinfunction "2_2") (pintype "power_in"))
      (node (ref "C58") (pin "2") (pinfunction "2_2") (pintype "power_in"))
      (node (ref "D11") (pin "4") (pinfunction "COMP_4") (pintype "passive"))
    )
    (net (code "44") (name "Net-(D11-FB)") (class "Default")
      (node (ref "C62") (pin "2") (pinfunction "2_2") (pintype "power_in"))
      (node (ref "D11") (pin "5") (pinfunction "FB_5") (pintype "passive"))
      (node (ref "R58") (pin "2") (pinfunction "2_2") (pintype "passive"))
      (node (ref "R62") (pin "2") (pinfunction "2_2") (pintype "passive"))
    )
    (net (code "45") (name "Net-(D11-OUT)") (class "Default")
      (node (ref "D11") (pin "1") (pinfunction "OUT_1") (pintype "passive"))
      (node (ref "L3") (pin "2") (pinfunction "2_2") (pintype "passive"))
      (node (ref "VD44") (pin "2") (pinfunction "2_2") (pintype "passive"))
    )
    (net (code "46") (name "Net-(D12-IN)") (class "Default")
      (node (ref "C49") (pin "2") (pinfunction "2_2") (pintype "power_in"))
      (node (ref "D12") (pin "3") (pinfunction "IN_3") (pintype "power_in"))
      (node (ref "FB1") (pin "1") (pinfunction "1_1") (pintype "passive"))
    )
    (net (code "47") (name "Net-(D14-CT)") (class "Default")
      (node (ref "C70") (pin "2") (pinfunction "2_2") (pintype "power_in"))
      (node (ref "D14") (pin "5") (pinfunction "CT_5") (pintype "passive"))
    )
    (net (code "48") (name "Net-(D14-CTRL)") (class "Default")
      (node (ref "C64") (pin "2") (pinfunction "2_2") (pintype "power_in"))
      (node (ref "D14") (pin "13") (pinfunction "CTRL_13") (pintype "passive"))
      (node (ref "D14") (pin "14") (pinfunction "REF_14") (pintype "passive"))
      (node (ref "D14") (pin "15") (pinfunction "IN2-_15") (pintype "passive"))
      (node (ref "D14") (pin "2") (pinfunction "IN1-_2") (pintype "passive"))
      (node (ref "R63") (pin "1") (pinfunction "1_1") (pintype "passive"))
      (node (ref "U1") (pin "4") (pinfunction "C_4") (pintype "passive"))
      (node (ref "VT13") (pin "2") (pinfunction "E_2") (pintype "passive"))
    )
    (net (code "49") (name "Net-(D14-DTC)") (class "Default")
      (node (ref "C64") (pin "1") (pinfunction "1_1") (pintype "power_in"))
      (node (ref "D14") (pin "4") (pinfunction "DTC_4") (pintype "passive"))
      (node (ref "R76") (pin "2") (pinfunction "2_2") (pintype "passive"))
      (node (ref "VT13") (pin "3") (pinfunction "C_3") (pintype "passive"))
    )
    (net (code "50") (name "Net-(D14-FB)") (class "Default")
      (node (ref "D14") (pin "3") (pinfunction "FB_3") (pintype "passive"))
      (node (ref "R78") (pin "2") (pinfunction "2_2") (pintype "passive"))
      (node (ref "U1") (pin "3") (pinfunction "E_3") (pintype "passive"))
    )
    (net (code "51") (name "Net-(D14-RT)") (class "Default")
      (node (ref "D14") (pin "6") (pinfunction "RT_6") (pintype "passive"))
      (node (ref "R77") (pin "2") (pinfunction "2_2") (pintype "passive"))
    )
    (net (code "52") (name "Net-(D15-IN+)") (class "Default")
      (node (ref "D15") (pin "3") (pinfunction "IN+_3") (pintype "input"))
      (node (ref "R66") (pin "1") (pinfunction "1_1") (pintype "passive"))
    )
    (net (code "53") (name "Net-(D15-IN-)") (class "Default")
      (node (ref "D15") (pin "4") (pinfunction "IN-_4") (pintype "input"))
      (node (ref "R64") (pin "1") (pinfunction "1_1") (pintype "passive"))
      (node (ref "R74") (pin "3") (pinfunction "3_3") (pintype "passive"))
    )
    (net (code "54") (name "Net-(D15-OUT)") (class "Default")
      (node (ref "D15") (pin "1") (pinfunction "OUT_1") (pintype "output"))
      (node (ref "R67") (pin "2") (pinfunction "2_2") (pintype "passive"))
    )
    (net (code "55") (name "Net-(D16-IN+)") (class "Default")
      (node (ref "D16") (pin "3") (pinfunction "IN+_3") (pintype "input"))
      (node (ref "R68") (pin "1") (pinfunction "1_1") (pintype "passive"))
    )
    (net (code "56") (name "Net-(D16-IN-)") (class "Default")
      (node (ref "D16") (pin "4") (pinfunction "IN-_4") (pintype "input"))
      (node (ref "R65") (pin "1") (pinfunction "1_1") (pintype "passive"))
      (node (ref "R75") (pin "3") (pinfunction "3_3") (pintype "passive"))
    )
    (net (code "57") (name "Net-(D16-OUT)") (class "Default")
      (node (ref "D16") (pin "1") (pinfunction "OUT_1") (pintype "output"))
      (node (ref "R69") (pin "2") (pinfunction "2_2") (pintype "passive"))
    )
    (net (code "58") (name "Net-(L1-Pad1)") (class "Default")
      (node (ref "L1") (pin "1") (pinfunction "1_1") (pintype "passive"))
      (node (ref "VD18") (pin "2") (pinfunction "2_2") (pintype "passive"))
      (node (ref "VD19") (pin "2") (pinfunction "2_2") (pintype "passive"))
      (node (ref "VD20") (pin "2") (pinfunction "2_2") (pintype "passive"))
      (node (ref "VD21") (pin "2") (pinfunction "2_2") (pintype "passive"))
    )
    (net (code "59") (name "Net-(R14-Pad2)") (class "Default")
      (node (ref "R14") (pin "2") (pinfunction "2_2") (pintype "passive"))
      (node (ref "R23") (pin "1") (pinfunction "1_1") (pintype "passive"))
    )
    (net (code "60") (name "Net-(T1-Pad4)") (class "Default")
      (node (ref "T1") (pin "4") (pinfunction "4_4") (pintype "power_in"))
      (node (ref "T2") (pin "6") (pinfunction "6_6") (pintype "power_in"))
    )
    (net (code "61") (name "Net-(T1-Pad6)") (class "Default")
      (node (ref "T1") (pin "6") (pinfunction "6_6") (pintype "power_in"))
      (node (ref "VD20") (pin "1") (pinfunction "1_1") (pintype "passive"))
      (node (ref "VD21") (pin "1") (pinfunction "1_1") (pintype "passive"))
      (node (ref "VD25") (pin "2") (pinfunction "2_2") (pintype "passive"))
      (node (ref "VD26") (pin "2") (pinfunction "2_2") (pintype "passive"))
    )
    (net (code "62") (name "Net-(T2-Pad4)") (class "Default")
      (node (ref "T2") (pin "4") (pinfunction "4_4") (pintype "power_in"))
      (node (ref "VD18") (pin "1") (pinfunction "1_1") (pintype "passive"))
      (node (ref "VD19") (pin "1") (pinfunction "1_1") (pintype "passive"))
      (node (ref "VD23") (pin "2") (pinfunction "2_2") (pintype "passive"))
      (node (ref "VD24") (pin "2") (pinfunction "2_2") (pintype "passive"))
    )
    (net (code "63") (name "Net-(U1A-A)") (class "Default")
      (node (ref "R15") (pin "1") (pinfunction "1_1") (pintype "passive"))
      (node (ref "R24") (pin "2") (pinfunction "2_2") (pintype "passive"))
      (node (ref "U1") (pin "1") (pinfunction "A_1") (pintype "passive"))
    )
    (net (code "64") (name "Net-(U1A-C)") (class "Default")
      (node (ref "C29") (pin "2") (pinfunction "2_2") (pintype "power_in"))
      (node (ref "R24") (pin "1") (pinfunction "1_1") (pintype "passive"))
      (node (ref "R32") (pin "1") (pinfunction "1_1") (pintype "passive"))
      (node (ref "U1") (pin "2") (pinfunction "C_2") (pintype "passive"))
      (node (ref "VD22") (pin "1") (pinfunction "1_1") (pintype "power_in"))
    )
    (net (code "65") (name "Net-(VD13-C)") (class "Default")
      (node (ref "R17") (pin "1") (pinfunction "1_1") (pintype "passive"))
      (node (ref "R27") (pin "2") (pinfunction "2_2") (pintype "passive"))
      (node (ref "VD13") (pin "2") (pinfunction "C_2") (pintype "passive"))
      (node (ref "VD6") (pin "1") (pinfunction "1_1") (pintype "passive"))
      (node (ref "VT2") (pin "1") (pinfunction "G_1") (pintype "passive"))
    )
    (net (code "66") (name "Net-(VD14-C)") (class "Default")
      (node (ref "R18") (pin "1") (pinfunction "1_1") (pintype "passive"))
      (node (ref "R28") (pin "2") (pinfunction "2_2") (pintype "passive"))
      (node (ref "VD14") (pin "2") (pinfunction "C_2") (pintype "passive"))
      (node (ref "VD7") (pin "1") (pinfunction "1_1") (pintype "passive"))
      (node (ref "VT3") (pin "1") (pinfunction "G_1") (pintype "passive"))
    )
    (net (code "67") (name "Net-(VD15-C)") (class "Default")
      (node (ref "R19") (pin "1") (pinfunction "1_1") (pintype "passive"))
      (node (ref "R29") (pin "2") (pinfunction "2_2") (pintype "passive"))
      (node (ref "VD15") (pin "2") (pinfunction "C_2") (pintype "passive"))
      (node (ref "VD8") (pin "1") (pinfunction "1_1") (pintype "passive"))
      (node (ref "VT4") (pin "1") (pinfunction "G_1") (pintype "passive"))
    )
    (net (code "68") (name "Net-(VD16-C)") (class "Default")
      (node (ref "R20") (pin "1") (pinfunction "1_1") (pintype "passive"))
      (node (ref "R30") (pin "2") (pinfunction "2_2") (pintype "passive"))
      (node (ref "VD16") (pin "2") (pinfunction "C_2") (pintype "passive"))
      (node (ref "VD9") (pin "1") (pinfunction "1_1") (pintype "passive"))
      (node (ref "VT5") (pin "1") (pinfunction "G_1") (pintype "passive"))
    )
    (net (code "69") (name "Net-(VD17-C)") (class "Default")
      (node (ref "R21") (pin "1") (pinfunction "1_1") (pintype "passive"))
      (node (ref "R31") (pin "2") (pinfunction "2_2") (pintype "passive"))
      (node (ref "VD10") (pin "1") (pinfunction "1_1") (pintype "passive"))
      (node (ref "VD17") (pin "2") (pinfunction "C_2") (pintype "passive"))
      (node (ref "VT6") (pin "1") (pinfunction "G_1") (pintype "passive"))
    )
    (net (code "70") (name "Net-(VD38-C)") (class "Default")
      (node (ref "R44") (pin "1") (pinfunction "1_1") (pintype "passive"))
      (node (ref "R52") (pin "2") (pinfunction "2_2") (pintype "passive"))
      (node (ref "VD31") (pin "1") (pinfunction "1_1") (pintype "passive"))
      (node (ref "VD38") (pin "2") (pinfunction "C_2") (pintype "passive"))
      (node (ref "VT8") (pin "1") (pinfunction "G_1") (pintype "passive"))
    )
    (net (code "71") (name "Net-(VD39-C)") (class "Default")
      (node (ref "R45") (pin "1") (pinfunction "1_1") (pintype "passive"))
      (node (ref "R53") (pin "2") (pinfunction "2_2") (pintype "passive"))
      (node (ref "VD32") (pin "1") (pinfunction "1_1") (pintype "passive"))
      (node (ref "VD39") (pin "2") (pinfunction "C_2") (pintype "passive"))
      (node (ref "VT9") (pin "1") (pinfunction "G_1") (pintype "passive"))
    )
    (net (code "72") (name "Net-(VD40-C)") (class "Default")
      (node (ref "R46") (pin "1") (pinfunction "1_1") (pintype "passive"))
      (node (ref "R54") (pin "2") (pinfunction "2_2") (pintype "passive"))
      (node (ref "VD33") (pin "1") (pinfunction "1_1") (pintype "passive"))
      (node (ref "VD40") (pin "2") (pinfunction "C_2") (pintype "passive"))
      (node (ref "VT10") (pin "1") (pinfunction "G_1") (pintype "passive"))
    )
    (net (code "73") (name "Net-(VD41-C)") (class "Default")
      (node (ref "R47") (pin "1") (pinfunction "1_1") (pintype "passive"))
      (node (ref "R55") (pin "2") (pinfunction "2_2") (pintype "passive"))
      (node (ref "VD34") (pin "1") (pinfunction "1_1") (pintype "passive"))
      (node (ref "VD41") (pin "2") (pinfunction "C_2") (pintype "passive"))
      (node (ref "VT11") (pin "1") (pinfunction "G_1") (pintype "passive"))
    )
    (net (code "74") (name "Net-(VD42-C)") (class "Default")
      (node (ref "R48") (pin "1") (pinfunction "1_1") (pintype "passive"))
      (node (ref "R56") (pin "2") (pinfunction "2_2") (pintype "passive"))
      (node (ref "VD35") (pin "1") (pinfunction "1_1") (pintype "passive"))
      (node (ref "VD42") (pin "2") (pinfunction "C_2") (pintype "passive"))
      (node (ref "VT12") (pin "1") (pinfunction "G_1") (pintype "passive"))
    )
    (net (code "75") (name "Net-(VD45-A)") (class "Default")
      (node (ref "VD45") (pin "1") (pinfunction "A_1") (pintype "passive"))
      (node (ref "VT16") (pin "3") (pinfunction "C_3") (pintype "passive"))
    )
    (net (code "76") (name "Net-(VD45-C)") (class "Default")
      (node (ref "R80") (pin "1") (pinfunction "1_1") (pintype "passive"))
      (node (ref "VD45") (pin "2") (pinfunction "C_2") (pintype "passive"))
    )
    (net (code "77") (name "Net-(VD46-C)") (class "Default")
      (node (ref "R81") (pin "1") (pinfunction "1_1") (pintype "passive"))
      (node (ref "VD46") (pin "2") (pinfunction "C_2") (pintype "passive"))
    )
    (net (code "78") (name "Net-(VD47-C)") (class "Default")
      (node (ref "R82") (pin "1") (pinfunction "1_1") (pintype "passive"))
      (node (ref "VD47") (pin "2") (pinfunction "C_2") (pintype "passive"))
    )
    (net (code "79") (name "Net-(VT14-D)") (class "Default")
      (node (ref "VT14") (pin "2") (pinfunction "D_2") (pintype "passive"))
      (node (ref "X4") (pin "2") (pinfunction "2_2") (pintype "passive"))
    )
    (net (code "80") (name "Net-(VT14-G)") (class "Default")
      (node (ref "R67") (pin "1") (pinfunction "1_1") (pintype "passive"))
      (node (ref "R72") (pin "2") (pinfunction "2_2") (pintype "passive"))
      (node (ref "VT14") (pin "1") (pinfunction "G_1") (pintype "passive"))
    )
    (net (code "81") (name "Net-(VT15-D)") (class "Default")
      (node (ref "VT15") (pin "2") (pinfunction "D_2") (pintype "passive"))
      (node (ref "X6") (pin "2") (pinfunction "2_2") (pintype "passive"))
    )
    (net (code "82") (name "Net-(VT15-G)") (class "Default")
      (node (ref "R69") (pin "1") (pinfunction "1_1") (pintype "passive"))
      (node (ref "R73") (pin "2") (pinfunction "2_2") (pintype "passive"))
      (node (ref "VT15") (pin "1") (pinfunction "G_1") (pintype "passive"))
    )
    (net (code "83") (name "VCCH_5V") (class "Default")
      (node (ref "C61") (pin "2") (pinfunction "2_2") (pintype "power_in"))
      (node (ref "D13") (pin "6") (pinfunction "VOUT_6") (pintype "power_in"))
      (node (ref "R15") (pin "2") (pinfunction "2_2") (pintype "passive"))
    )
    (net (code "84") (name "VCCH_380V") (class "Default")
      (node (ref "C30") (pin "1") (pinfunction "1_1") (pintype "power_in"))
      (node (ref "C31") (pin "1") (pinfunction "1_1") (pintype "power_in"))
      (node (ref "C32") (pin "1") (pinfunction "1_1") (pintype "power_in"))
      (node (ref "C33") (pin "1") (pinfunction "1_1") (pintype "power_in"))
      (node (ref "L1") (pin "2") (pinfunction "2_2") (pintype "passive"))
      (node (ref "R14") (pin "1") (pinfunction "1_1") (pintype "passive"))
      (node (ref "R83") (pin "1") (pinfunction "1_1") (pintype "passive"))
      (node (ref "X7") (pin "1") (pinfunction "1_1") (pintype "passive"))
    )
    (net (code "85") (name "VCC_5V") (class "Default")
      (node (ref "C18") (pin "2") (pinfunction "2_2") (pintype "power_in"))
      (node (ref "C20") (pin "2") (pinfunction "2_2") (pintype "power_in"))
      (node (ref "C22") (pin "2") (pinfunction "2_2") (pintype "power_in"))
      (node (ref "C35") (pin "2") (pinfunction "2_2") (pintype "power_in"))
      (node (ref "C37") (pin "2") (pinfunction "2_2") (pintype "power_in"))
      (node (ref "C50") (pin "2") (pinfunction "2_2") (pintype "power_in"))
      (node (ref "C60") (pin "2") (pinfunction "2_2") (pintype "power_in"))
      (node (ref "C67") (pin "2") (pinfunction "2_2") (pintype "power_in"))
      (node (ref "C68") (pin "2") (pinfunction "2_2") (pintype "power_in"))
      (node (ref "D1") (pin "5") (pinfunction "VDD_5") (pintype "power_in"))
      (node (ref "D12") (pin "2") (pinfunction "OUT_2") (pintype "passive"))
      (node (ref "D12") (pin "4") (pinfunction "OUT_4") (pintype "passive"))
      (node (ref "D13") (pin "1") (pinfunction "VIN_1") (pintype "power_in"))
      (node (ref "D15") (pin "5") (pinfunction "VDD_5") (pintype "power_in"))
      (node (ref "D16") (pin "5") (pinfunction "VDD_5") (pintype "power_in"))
      (node (ref "D2") (pin "5") (pinfunction "VDD_5") (pintype "power_in"))
      (node (ref "D3") (pin "5") (pinfunction "VCC_5") (pintype "power_in"))
      (node (ref "D6") (pin "5") (pinfunction "VDD_5") (pintype "power_in"))
      (node (ref "D7") (pin "5") (pinfunction "VCC_5") (pintype "power_in"))
      (node (ref "R1") (pin "2") (pinfunction "2_2") (pintype "passive"))
      (node (ref "R33") (pin "2") (pinfunction "2_2") (pintype "passive"))
      (node (ref "R6") (pin "2") (pinfunction "2_2") (pintype "passive"))
      (node (ref "R64") (pin "2") (pinfunction "2_2") (pintype "passive"))
      (node (ref "R65") (pin "2") (pinfunction "2_2") (pintype "passive"))
      (node (ref "R79") (pin "1") (pinfunction "1_1") (pintype "passive"))
      (node (ref "VD46") (pin "1") (pinfunction "A_1") (pintype "passive"))
      (node (ref "VT16") (pin "2") (pinfunction "E_2") (pintype "passive"))
      (node (ref "X3") (pin "1") (pinfunction "1_1") (pintype "passive"))
      (node (ref "X5") (pin "1") (pinfunction "1_1") (pintype "passive"))
    )
    (net (code "86") (name "VCC_12V") (class "Default")
      (node (ref "C24") (pin "2") (pinfunction "2_2") (pintype "power_in"))
      (node (ref "C25") (pin "2") (pinfunction "2_2") (pintype "power_in"))
      (node (ref "C26") (pin "1") (pinfunction "1_1") (pintype "power_in"))
      (node (ref "C27") (pin "1") (pinfunction "1_1") (pintype "power_in"))
      (node (ref "C39") (pin "2") (pinfunction "2_2") (pintype "power_in"))
      (node (ref "C40") (pin "2") (pinfunction "2_2") (pintype "power_in"))
      (node (ref "C41") (pin "1") (pinfunction "1_1") (pintype "power_in"))
      (node (ref "C42") (pin "1") (pinfunction "1_1") (pintype "power_in"))
      (node (ref "C43") (pin "1") (pinfunction "1_1") (pintype "power_in"))
      (node (ref "C44") (pin "2") (pinfunction "2_2") (pintype "power_in"))
      (node (ref "C45") (pin "2") (pinfunction "2_2") (pintype "power_in"))
      (node (ref "C69") (pin "2") (pinfunction "2_2") (pintype "power_in"))
      (node (ref "D14") (pin "11") (pinfunction "VC_11") (pintype "passive"))
      (node (ref "D14") (pin "12") (pinfunction "VCC_12") (pintype "passive"))
      (node (ref "D5") (pin "1") (pinfunction "VDD_1") (pintype "passive"))
      (node (ref "D5") (pin "8") (pinfunction "VDD_8") (pintype "passive"))
      (node (ref "D9") (pin "1") (pinfunction "VDD_1") (pintype "passive"))
      (node (ref "D9") (pin "8") (pinfunction "VDD_8") (pintype "passive"))
      (node (ref "L2") (pin "1") (pinfunction "1_1") (pintype "passive"))
      (node (ref "R57") (pin "1") (pinfunction "1_1") (pintype "passive"))
      (node (ref "VD2") (pin "2") (pinfunction "2_2") (pintype "passive"))
      (node (ref "VD27") (pin "2") (pinfunction "2_2") (pintype "passive"))
      (node (ref "VD47") (pin "1") (pinfunction "A_1") (pintype "passive"))
      (node (ref "X4") (pin "1") (pinfunction "1_1") (pintype "passive"))
      (node (ref "X6") (pin "1") (pinfunction "1_1") (pintype "passive"))
    )
    (net (code "87") (name "VCC_IN") (class "Default")
      (node (ref "C1") (pin "1") (pinfunction "1_1") (pintype "power_in"))
      (node (ref "C10") (pin "1") (pinfunction "1_1") (pintype "power_in"))
      (node (ref "C11") (pin "1") (pinfunction "1_1") (pintype "power_in"))
      (node (ref "C12") (pin "1") (pinfunction "1_1") (pintype "power_in"))
      (node (ref "C13") (pin "1") (pinfunction "1_1") (pintype "power_in"))
      (node (ref "C14") (pin "1") (pinfunction "1_1") (pintype "power_in"))
      (node (ref "C15") (pin "1") (pinfunction "1_1") (pintype "power_in"))
      (node (ref "C16") (pin "1") (pinfunction "1_1") (pintype "power_in"))
      (node (ref "C17") (pin "1") (pinfunction "1_1") (pintype "power_in"))
      (node (ref "C2") (pin "1") (pinfunction "1_1") (pintype "power_in"))
      (node (ref "C3") (pin "1") (pinfunction "1_1") (pintype "power_in"))
      (node (ref "C4") (pin "1") (pinfunction "1_1") (pintype "power_in"))
      (node (ref "C5") (pin "1") (pinfunction "1_1") (pintype "power_in"))
      (node (ref "C51") (pin "2") (pinfunction "2_2") (pintype "power_in"))
      (node (ref "C52") (pin "2") (pinfunction "2_2") (pintype "power_in"))
      (node (ref "C54") (pin "2") (pinfunction "2_2") (pintype "power_in"))
      (node (ref "C55") (pin "2") (pinfunction "2_2") (pintype "power_in"))
      (node (ref "C6") (pin "1") (pinfunction "1_1") (pintype "power_in"))
      (node (ref "C7") (pin "1") (pinfunction "1_1") (pintype "power_in"))
      (node (ref "C8") (pin "1") (pinfunction "1_1") (pintype "power_in"))
      (node (ref "C9") (pin "1") (pinfunction "1_1") (pintype "power_in"))
      (node (ref "D10") (pin "8") (pinfunction "VCC_8") (pintype "passive"))
      (node (ref "D11") (pin "8") (pinfunction "VCC_8") (pintype "passive"))
      (node (ref "R2") (pin "1") (pinfunction "1_1") (pintype "passive"))
      (node (ref "T1") (pin "2") (pinfunction "2_2") (pintype "power_in"))
      (node (ref "T2") (pin "2") (pinfunction "2_2") (pintype "power_in"))
      (node (ref "X1") (pin "1") (pinfunction "1_1") (pintype "passive"))
    )
    (net (code "88") (name "unconnected-(D10-SYNC-Pad2)") (class "Default")
      (node (ref "D10") (pin "2") (pinfunction "SYNC_2") (pintype "passive"))
    )
    (net (code "89") (name "unconnected-(D10-VREF-Pad6)") (class "Default")
      (node (ref "D10") (pin "6") (pinfunction "VREF_6") (pintype "passive"))
    )
    (net (code "90") (name "unconnected-(D11-SYNC-Pad2)") (class "Default")
      (node (ref "D11") (pin "2") (pinfunction "SYNC_2") (pintype "passive"))
    )
    (net (code "91") (name "unconnected-(D11-VREF-Pad6)") (class "Default")
      (node (ref "D11") (pin "6") (pinfunction "VREF_6") (pintype "passive"))
    )
    (net (code "92") (name "unconnected-(T1-Pad5)") (class "Default")
      (node (ref "T1") (pin "5") (pinfunction "5_5") (pintype "power_in"))
    )
    (net (code "93") (name "unconnected-(T2-Pad5)") (class "Default")
      (node (ref "T2") (pin "5") (pinfunction "5_5") (pintype "power_in"))
    )
  )
)
